# CPU_PCIE_USB_HDMI_EXT_PCIEX2_mPCIeX2.net
KiCad netlist of a schematic drawn in Altium Designer
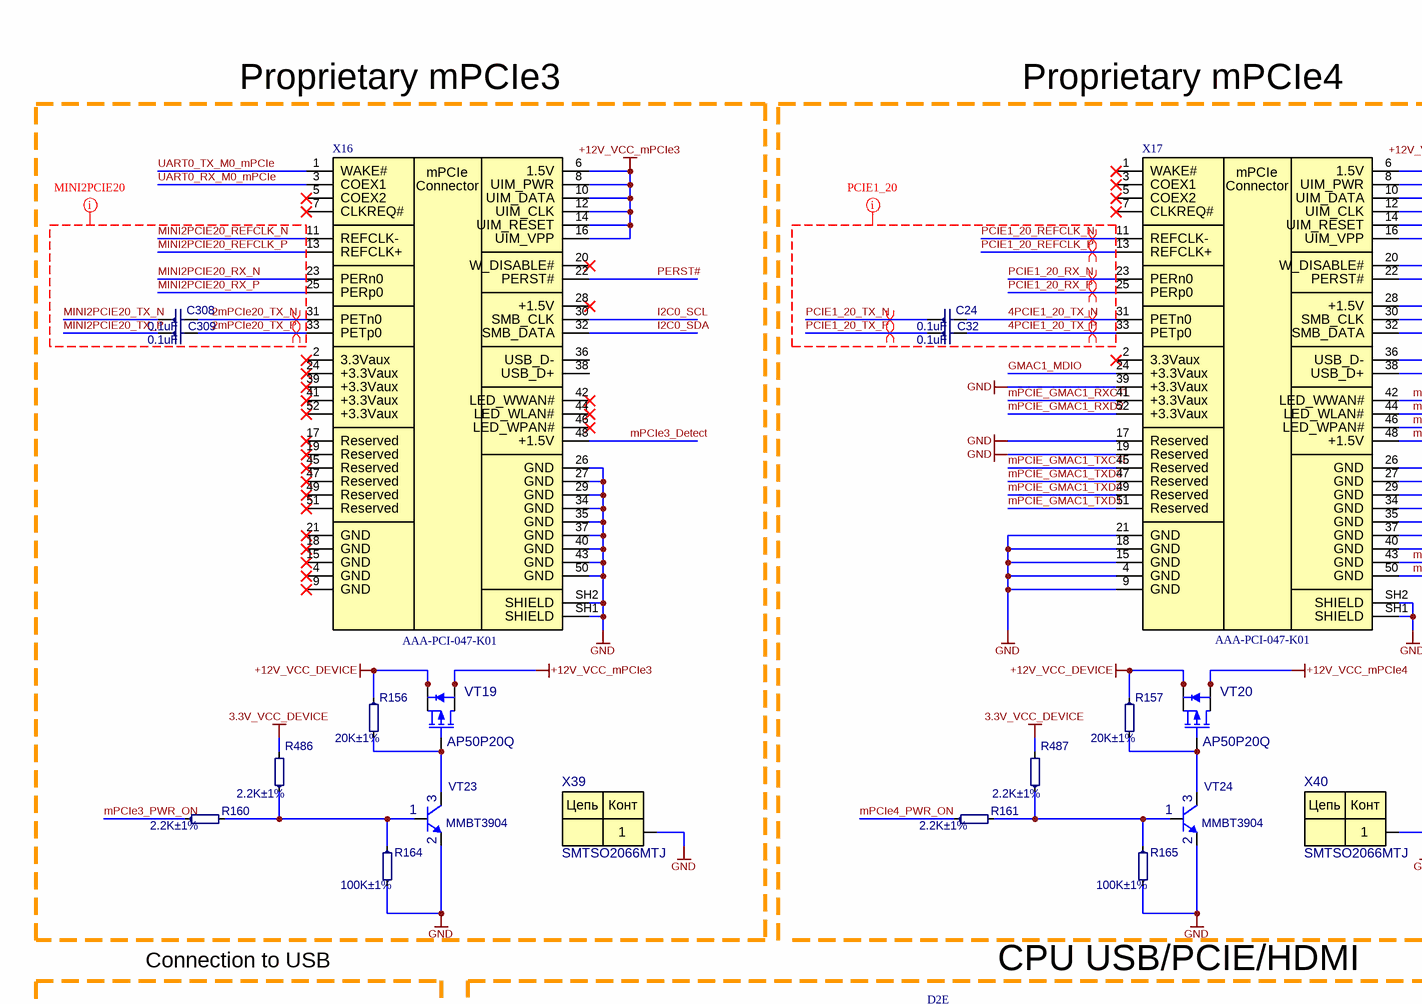
[diagram p0: CPU_PCIE_USB_HDMI_EXT_PCIEX2_mPCIeX2.SchDoc, top left]
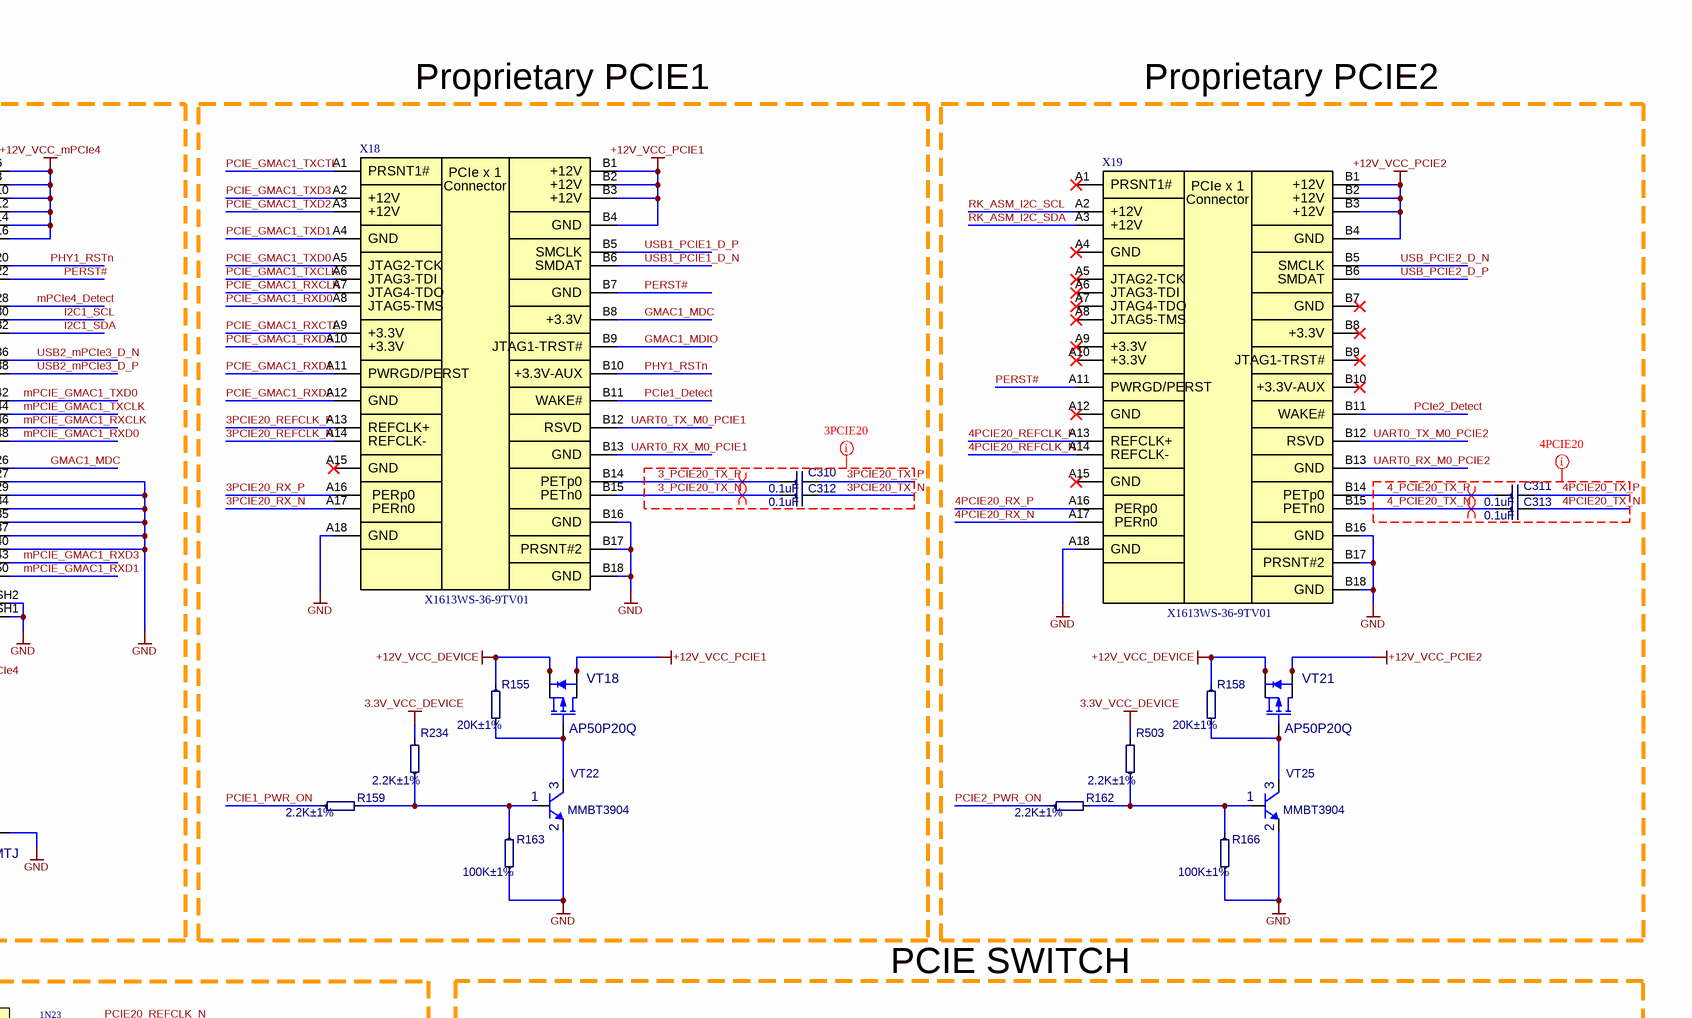
[diagram p1: CPU_PCIE_USB_HDMI_EXT_PCIEX2_mPCIeX2.SchDoc, top right]
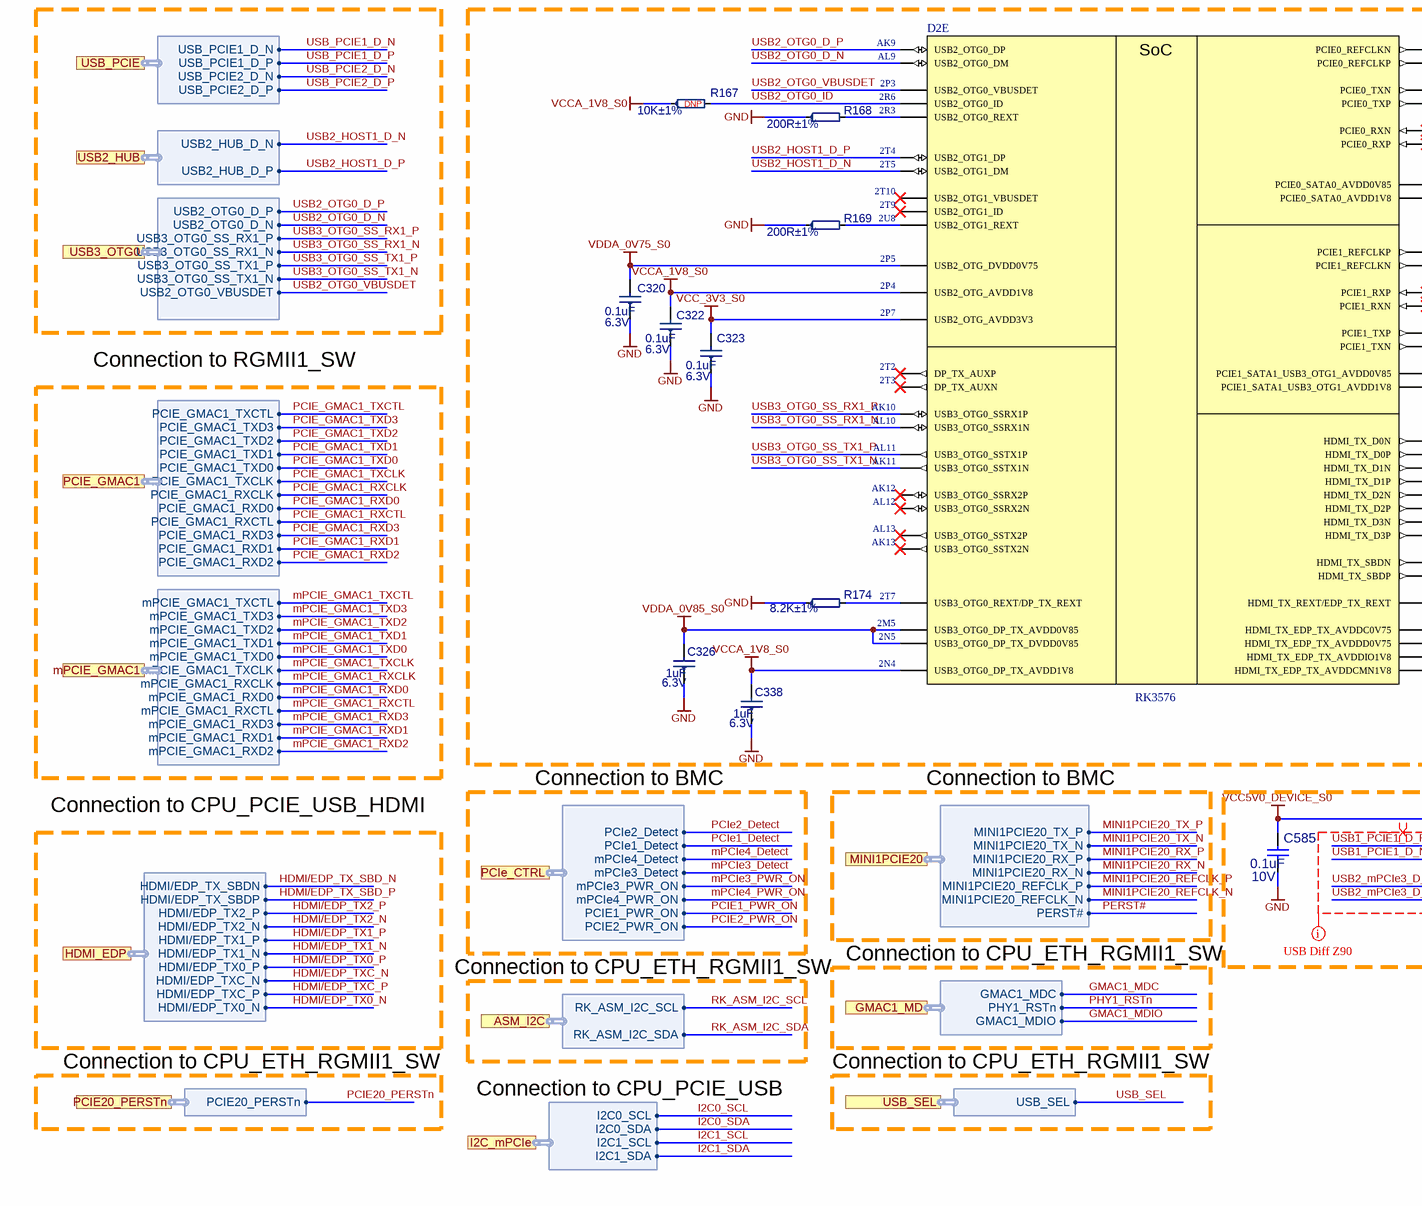
[diagram p2: CPU_PCIE_USB_HDMI_EXT_PCIEX2_mPCIeX2.SchDoc, bottom left]
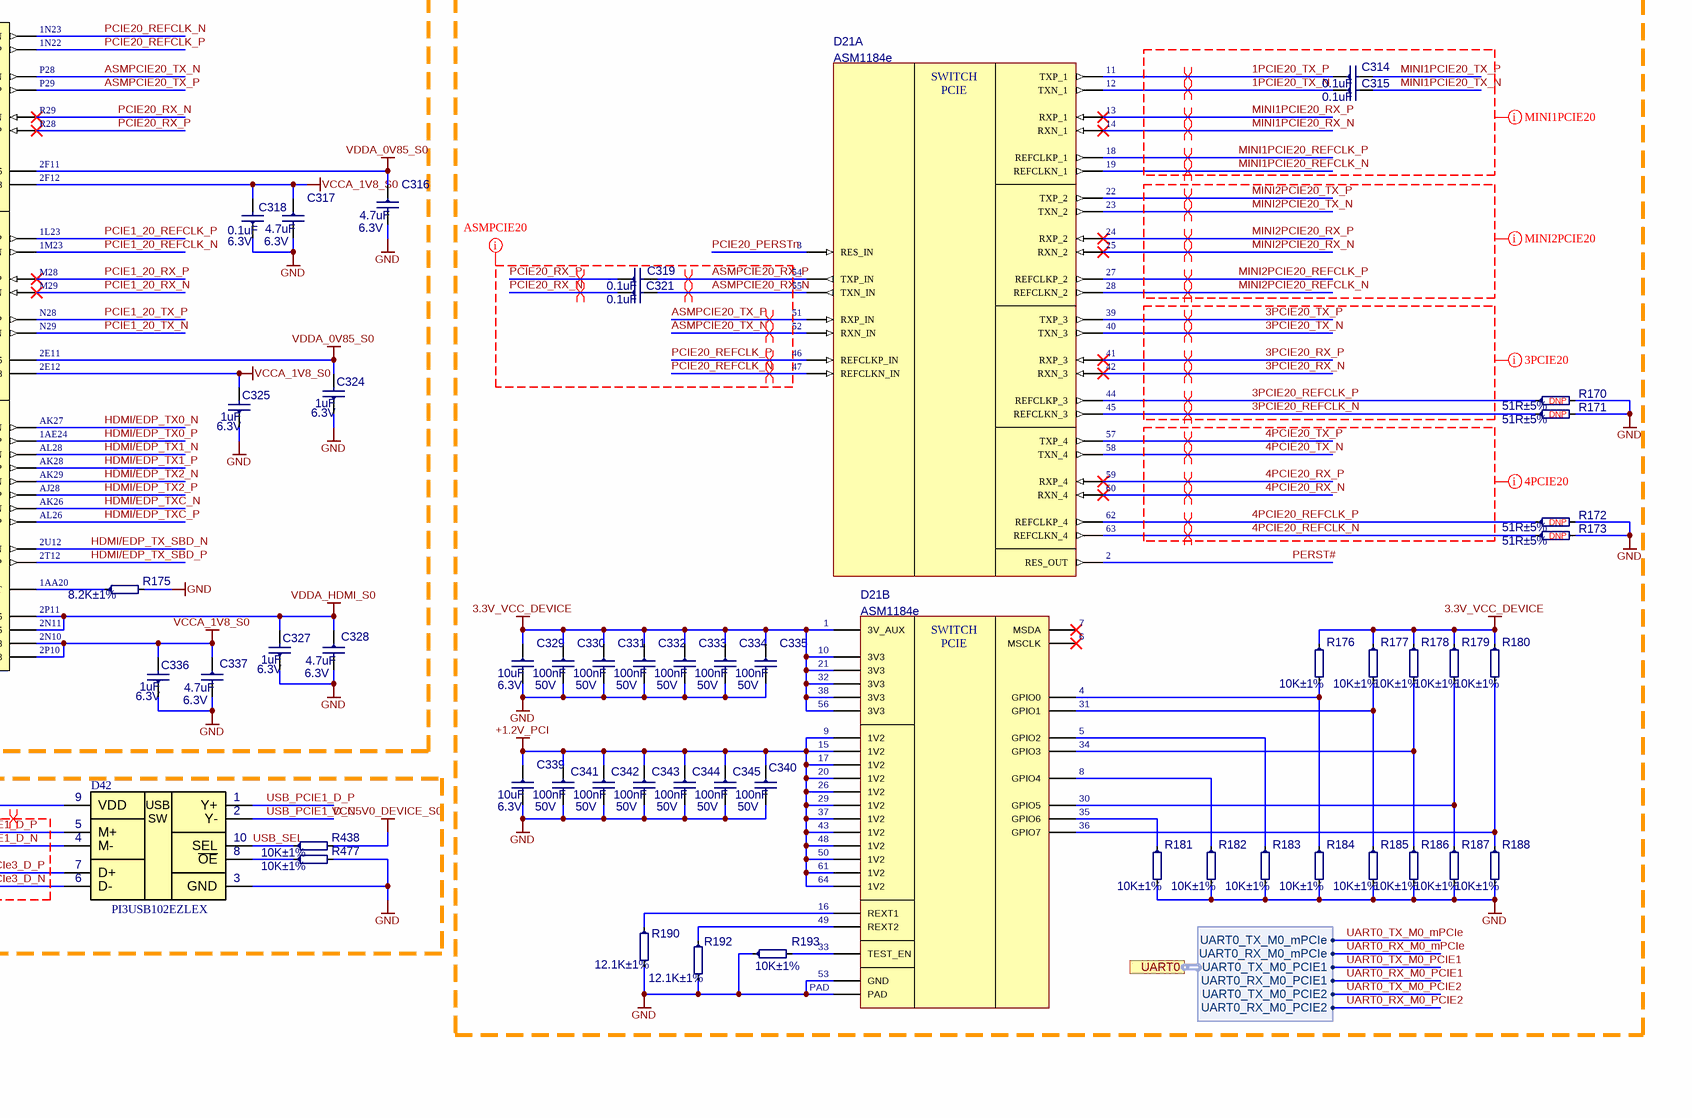
[diagram p3: CPU_PCIE_USB_HDMI_EXT_PCIEX2_mPCIeX2.SchDoc, bottom right]

(export (version "E")
  (design (tool "Eeschema 10.0.6"))
  (components
    (comp (ref "C24")
      (value "0.1uF")
      (footprint "C0201")
      (fields
        (field (name "VOLTAGE") "25V")
        (field (name "PART NUMBER") "0201-X5R-25V-0.1uF±10%")
        (field (name "TOLERANCE") "10%")
      )
      (libsource (lib "ATB") (part "C"))
    )
    (comp (ref "C32")
      (value "0.1uF")
      (footprint "C0201")
      (fields
        (field (name "VOLTAGE") "25V")
        (field (name "PART NUMBER") "0201-X5R-25V-0.1uF±10%")
        (field (name "TOLERANCE") "10%")
      )
      (libsource (lib "ATB") (part "C"))
    )
    (comp (ref "C308")
      (value "0.1uF")
      (footprint "C0201")
      (fields
        (field (name "VOLTAGE") "25V")
        (field (name "PART NUMBER") "0201-X5R-25V-0.1uF±10%")
        (field (name "TOLERANCE") "10%")
      )
      (libsource (lib "ATB") (part "C"))
    )
    (comp (ref "C309")
      (value "0.1uF")
      (footprint "C0201")
      (fields
        (field (name "VOLTAGE") "25V")
        (field (name "PART NUMBER") "0201-X5R-25V-0.1uF±10%")
        (field (name "TOLERANCE") "10%")
      )
      (libsource (lib "ATB") (part "C"))
    )
    (comp (ref "C310")
      (value "0.1uF")
      (footprint "C0201")
      (fields
        (field (name "VOLTAGE") "25V")
        (field (name "PART NUMBER") "0201-X5R-25V-0.1uF±10%")
        (field (name "TOLERANCE") "10%")
      )
      (libsource (lib "ATB") (part "C"))
    )
    (comp (ref "C311")
      (value "0.1uF")
      (footprint "C0201")
      (fields
        (field (name "VOLTAGE") "25V")
        (field (name "PART NUMBER") "0201-X5R-25V-0.1uF±10%")
        (field (name "TOLERANCE") "10%")
      )
      (libsource (lib "ATB") (part "C"))
    )
    (comp (ref "C312")
      (value "0.1uF")
      (footprint "C0201")
      (fields
        (field (name "VOLTAGE") "25V")
        (field (name "PART NUMBER") "0201-X5R-25V-0.1uF±10%")
        (field (name "TOLERANCE") "10%")
      )
      (libsource (lib "ATB") (part "C"))
    )
    (comp (ref "C313")
      (value "0.1uF")
      (footprint "C0201")
      (fields
        (field (name "VOLTAGE") "25V")
        (field (name "PART NUMBER") "0201-X5R-25V-0.1uF±10%")
        (field (name "TOLERANCE") "10%")
      )
      (libsource (lib "ATB") (part "C"))
    )
    (comp (ref "C314")
      (value "0.1uF")
      (footprint "C0201")
      (fields
        (field (name "VOLTAGE") "25V")
        (field (name "PART NUMBER") "0201-X5R-25V-0.1uF±10%")
        (field (name "TOLERANCE") "10%")
      )
      (libsource (lib "ATB") (part "C"))
    )
    (comp (ref "C315")
      (value "0.1uF")
      (footprint "C0201")
      (fields
        (field (name "VOLTAGE") "25V")
        (field (name "PART NUMBER") "0201-X5R-25V-0.1uF±10%")
        (field (name "TOLERANCE") "10%")
      )
      (libsource (lib "ATB") (part "C"))
    )
    (comp (ref "C316")
      (value "4.7uF")
      (footprint "C0201")
      (fields
        (field (name "VOLTAGE") "6.3V")
        (field (name "PART NUMBER") "0201-X5R-6.3V-4.7uF±20%")
        (field (name "TOLERANCE") "20%")
        (field (name "MANUFACTURER") "Murata Electronics")
      )
      (libsource (lib "ATB") (part "C"))
    )
    (comp (ref "C317")
      (value "4.7uF")
      (footprint "C0201")
      (fields
        (field (name "VOLTAGE") "6.3V")
        (field (name "PART NUMBER") "0201-X5R-6.3V-4.7uF±20%")
        (field (name "TOLERANCE") "20%")
        (field (name "MANUFACTURER") "Murata Electronics")
      )
      (libsource (lib "ATB") (part "C"))
    )
    (comp (ref "C318")
      (value "0.1uF")
      (footprint "C0201")
      (fields
        (field (name "VOLTAGE") "6.3V")
        (field (name "PART NUMBER") "0201-X5R-6.3V-0.1uF±10%")
        (field (name "TOLERANCE") "10%")
        (field (name "MANUFACTURER") "Yageo")
      )
      (libsource (lib "ATB") (part "C"))
    )
    (comp (ref "C319")
      (value "0.1uF")
      (footprint "C0201")
      (fields
        (field (name "VOLTAGE") "25V")
        (field (name "PART NUMBER") "0201-X5R-25V-0.1uF±10%")
        (field (name "TOLERANCE") "10%")
      )
      (libsource (lib "ATB") (part "C"))
    )
    (comp (ref "C320")
      (value "0.1uF")
      (footprint "C0201")
      (fields
        (field (name "VOLTAGE") "6.3V")
        (field (name "PART NUMBER") "0201-X5R-6.3V-0.1uF±10%")
        (field (name "TOLERANCE") "10%")
        (field (name "MANUFACTURER") "Yageo")
      )
      (libsource (lib "ATB") (part "C"))
    )
    (comp (ref "C321")
      (value "0.1uF")
      (footprint "C0201")
      (fields
        (field (name "VOLTAGE") "25V")
        (field (name "PART NUMBER") "0201-X5R-25V-0.1uF±10%")
        (field (name "TOLERANCE") "10%")
      )
      (libsource (lib "ATB") (part "C"))
    )
    (comp (ref "C322")
      (value "0.1uF")
      (footprint "C0201")
      (fields
        (field (name "VOLTAGE") "6.3V")
        (field (name "PART NUMBER") "0201-X5R-6.3V-0.1uF±10%")
        (field (name "TOLERANCE") "10%")
        (field (name "MANUFACTURER") "Yageo")
      )
      (libsource (lib "ATB") (part "C"))
    )
    (comp (ref "C323")
      (value "0.1uF")
      (footprint "C0201")
      (fields
        (field (name "VOLTAGE") "6.3V")
        (field (name "PART NUMBER") "0201-X5R-6.3V-0.1uF±10%")
        (field (name "TOLERANCE") "10%")
        (field (name "MANUFACTURER") "Yageo")
      )
      (libsource (lib "ATB") (part "C"))
    )
    (comp (ref "C324")
      (value "1uF")
      (footprint "C0201")
      (fields
        (field (name "VOLTAGE") "6.3V")
        (field (name "PART NUMBER") "0201-X5R-6.3V-1uF±20%")
        (field (name "TOLERANCE") "20%")
        (field (name "MANUFACTURER") "Murata Electronics")
      )
      (libsource (lib "ATB") (part "C"))
    )
    (comp (ref "C325")
      (value "1uF")
      (footprint "C0201")
      (fields
        (field (name "VOLTAGE") "6.3V")
        (field (name "PART NUMBER") "0201-X5R-6.3V-1uF±20%")
        (field (name "TOLERANCE") "20%")
        (field (name "MANUFACTURER") "Murata Electronics")
      )
      (libsource (lib "ATB") (part "C"))
    )
    (comp (ref "C326")
      (value "1uF")
      (footprint "C0201")
      (fields
        (field (name "VOLTAGE") "6.3V")
        (field (name "PART NUMBER") "0201-X5R-6.3V-1uF±20%")
        (field (name "TOLERANCE") "20%")
        (field (name "MANUFACTURER") "Murata Electronics")
      )
      (libsource (lib "ATB") (part "C"))
    )
    (comp (ref "C327")
      (value "1uF")
      (footprint "C0201")
      (fields
        (field (name "VOLTAGE") "6.3V")
        (field (name "PART NUMBER") "0201-X5R-6.3V-1uF±20%")
        (field (name "TOLERANCE") "20%")
        (field (name "MANUFACTURER") "Murata Electronics")
      )
      (libsource (lib "ATB") (part "C"))
    )
    (comp (ref "C328")
      (value "4.7uF")
      (footprint "C0201")
      (fields
        (field (name "VOLTAGE") "6.3V")
        (field (name "PART NUMBER") "0201-X5R-6.3V-4.7uF±20%")
        (field (name "TOLERANCE") "20%")
        (field (name "MANUFACTURER") "Murata Electronics")
      )
      (libsource (lib "ATB") (part "C"))
    )
    (comp (ref "C329")
      (value "10uF")
      (footprint "C0402")
      (fields
        (field (name "VOLTAGE") "6.3V")
        (field (name "PART NUMBER") "0402-X5R-6.3V-10uF±20%")
        (field (name "TOLERANCE") "20%")
        (field (name "MANUFACTURER") "Yageo")
      )
      (libsource (lib "ATB") (part "C"))
    )
    (comp (ref "C330")
      (value "100nF")
      (footprint "C0402")
      (description "Ceramic Capacitor 0402 100nF ±10% 50V X7R")
      (fields
        (field (name "VOLTAGE") "50V")
        (field (name "PART NUMBER") "0402-X7R-50V-0.1uF±10%")
        (field (name "TOLERANCE") "10%")
      )
      (libsource (lib "ATB") (part "C"))
    )
    (comp (ref "C331")
      (value "100nF")
      (footprint "C0402")
      (description "Ceramic Capacitor 0402 100nF ±10% 50V X7R")
      (fields
        (field (name "VOLTAGE") "50V")
        (field (name "PART NUMBER") "0402-X7R-50V-0.1uF±10%")
        (field (name "TOLERANCE") "10%")
      )
      (libsource (lib "ATB") (part "C"))
    )
    (comp (ref "C332")
      (value "100nF")
      (footprint "C0402")
      (description "Ceramic Capacitor 0402 100nF ±10% 50V X7R")
      (fields
        (field (name "VOLTAGE") "50V")
        (field (name "PART NUMBER") "0402-X7R-50V-0.1uF±10%")
        (field (name "TOLERANCE") "10%")
      )
      (libsource (lib "ATB") (part "C"))
    )
    (comp (ref "C333")
      (value "100nF")
      (footprint "C0402")
      (description "Ceramic Capacitor 0402 100nF ±10% 50V X7R")
      (fields
        (field (name "VOLTAGE") "50V")
        (field (name "PART NUMBER") "0402-X7R-50V-0.1uF±10%")
        (field (name "TOLERANCE") "10%")
      )
      (libsource (lib "ATB") (part "C"))
    )
    (comp (ref "C334")
      (value "100nF")
      (footprint "C0402")
      (description "Ceramic Capacitor 0402 100nF ±10% 50V X7R")
      (fields
        (field (name "VOLTAGE") "50V")
        (field (name "PART NUMBER") "0402-X7R-50V-0.1uF±10%")
        (field (name "TOLERANCE") "10%")
      )
      (libsource (lib "ATB") (part "C"))
    )
    (comp (ref "C335")
      (value "100nF")
      (footprint "C0402")
      (description "Ceramic Capacitor 0402 100nF ±10% 50V X7R")
      (fields
        (field (name "VOLTAGE") "50V")
        (field (name "PART NUMBER") "0402-X7R-50V-0.1uF±10%")
        (field (name "TOLERANCE") "10%")
      )
      (libsource (lib "ATB") (part "C"))
    )
    (comp (ref "C336")
      (value "1uF")
      (footprint "C0201")
      (fields
        (field (name "VOLTAGE") "6.3V")
        (field (name "PART NUMBER") "0201-X5R-6.3V-1uF±20%")
        (field (name "TOLERANCE") "20%")
        (field (name "MANUFACTURER") "Murata Electronics")
      )
      (libsource (lib "ATB") (part "C"))
    )
    (comp (ref "C337")
      (value "4.7uF")
      (footprint "C0201")
      (fields
        (field (name "VOLTAGE") "6.3V")
        (field (name "PART NUMBER") "0201-X5R-6.3V-4.7uF±20%")
        (field (name "TOLERANCE") "20%")
        (field (name "MANUFACTURER") "Murata Electronics")
      )
      (libsource (lib "ATB") (part "C"))
    )
    (comp (ref "C338")
      (value "1uF")
      (footprint "C0201")
      (fields
        (field (name "VOLTAGE") "6.3V")
        (field (name "PART NUMBER") "0201-X5R-6.3V-1uF±20%")
        (field (name "TOLERANCE") "20%")
        (field (name "MANUFACTURER") "Murata Electronics")
      )
      (libsource (lib "ATB") (part "C"))
    )
    (comp (ref "C339")
      (value "10uF")
      (footprint "C0402")
      (fields
        (field (name "VOLTAGE") "6.3V")
        (field (name "PART NUMBER") "0402-X5R-6.3V-10uF±20%")
        (field (name "TOLERANCE") "20%")
        (field (name "MANUFACTURER") "Yageo")
      )
      (libsource (lib "ATB") (part "C"))
    )
    (comp (ref "C340")
      (value "100nF")
      (footprint "C0402")
      (description "Ceramic Capacitor 0402 100nF ±10% 50V X7R")
      (fields
        (field (name "VOLTAGE") "50V")
        (field (name "PART NUMBER") "0402-X7R-50V-0.1uF±10%")
        (field (name "TOLERANCE") "10%")
      )
      (libsource (lib "ATB") (part "C"))
    )
    (comp (ref "C341")
      (value "100nF")
      (footprint "C0402")
      (description "Ceramic Capacitor 0402 100nF ±10% 50V X7R")
      (fields
        (field (name "VOLTAGE") "50V")
        (field (name "PART NUMBER") "0402-X7R-50V-0.1uF±10%")
        (field (name "TOLERANCE") "10%")
      )
      (libsource (lib "ATB") (part "C"))
    )
    (comp (ref "C342")
      (value "100nF")
      (footprint "C0402")
      (description "Ceramic Capacitor 0402 100nF ±10% 50V X7R")
      (fields
        (field (name "VOLTAGE") "50V")
        (field (name "PART NUMBER") "0402-X7R-50V-0.1uF±10%")
        (field (name "TOLERANCE") "10%")
      )
      (libsource (lib "ATB") (part "C"))
    )
    (comp (ref "C343")
      (value "100nF")
      (footprint "C0402")
      (description "Ceramic Capacitor 0402 100nF ±10% 50V X7R")
      (fields
        (field (name "VOLTAGE") "50V")
        (field (name "PART NUMBER") "0402-X7R-50V-0.1uF±10%")
        (field (name "TOLERANCE") "10%")
      )
      (libsource (lib "ATB") (part "C"))
    )
    (comp (ref "C344")
      (value "100nF")
      (footprint "C0402")
      (description "Ceramic Capacitor 0402 100nF ±10% 50V X7R")
      (fields
        (field (name "VOLTAGE") "50V")
        (field (name "PART NUMBER") "0402-X7R-50V-0.1uF±10%")
        (field (name "TOLERANCE") "10%")
      )
      (libsource (lib "ATB") (part "C"))
    )
    (comp (ref "C345")
      (value "100nF")
      (footprint "C0402")
      (description "Ceramic Capacitor 0402 100nF ±10% 50V X7R")
      (fields
        (field (name "VOLTAGE") "50V")
        (field (name "PART NUMBER") "0402-X7R-50V-0.1uF±10%")
        (field (name "TOLERANCE") "10%")
      )
      (libsource (lib "ATB") (part "C"))
    )
    (comp (ref "C585")
      (value "0.1uF")
      (footprint "C0402")
      (fields
        (field (name "PART NUMBER") "0402-X5R-10V-0.1uF±10%")
        (field (name "VOLTAGE") "10V")
        (field (name "TOLERANCE") "10%")
        (field (name "MANUFACTURER") "Yageo")
      )
      (libsource (lib "") (part "C_1"))
    )
    (comp (ref "D2")
      (value "RK3576")
      (footprint "BGAFCCSP698L")
      (description "SoC 4xCortex-A72@2.2Ghz+4xCortex-A53@2Ghz, LPDDR4/4X/5/5X, SDIO/eMMC/UFS/FSPI, BGA 16.1x17.2x1.0mm")
      (fields (field (name "MANUFACTURER") "Rockship"))
      (libsource (lib "ATB") (part "RK3576"))
    )
    (comp (ref "D21")
      (value "ASM1184e")
      (footprint "QFN50X90X90X09-64T75x75")
      (description "Interface PCIE switch, PCIEx1 to 4xPCIEx1, 3.0V~3.6V, QFN-64 9.0x9.0x0.9mm 0.5mm pitch")
      (fields (field (name "MANUFACTURER") "ASMedia"))
      (libsource (lib "ATB") (part "ASM1184e"))
    )
    (comp (ref "D42")
      (value "PI3USB102EZLEX")
      (footprint "PI3USB102EZLEX")
      (description "USB 2.0 High-Speed (480 Mbps)  Switch with 5V Protection")
      (fields (field (name "MANUFACTURER") "Diodes"))
      (libsource (lib "LIB_RK") (part "PI3USB102EZLEX"))
    )
    (comp (ref "R155")
      (value "20K±1%")
      (footprint "R0402")
      (description "Chip Resistor 0402 20kΩ ±1% 50V ±100ppm/℃ Thick Film")
      (fields (field (name "PART NUMBER") "0402-0.0625W-20K-100ppm±1%") (field (name "TOLERANCE") "1%"))
      (libsource (lib "ATB") (part "R"))
    )
    (comp (ref "R156")
      (value "20K±1%")
      (footprint "R0402")
      (description "Chip Resistor 0402 20kΩ ±1% 50V ±100ppm/℃ Thick Film")
      (fields (field (name "PART NUMBER") "0402-0.0625W-20K-100ppm±1%") (field (name "TOLERANCE") "1%"))
      (libsource (lib "ATB") (part "R"))
    )
    (comp (ref "R157")
      (value "20K±1%")
      (footprint "R0402")
      (description "Chip Resistor 0402 20kΩ ±1% 50V ±100ppm/℃ Thick Film")
      (fields (field (name "PART NUMBER") "0402-0.0625W-20K-100ppm±1%") (field (name "TOLERANCE") "1%"))
      (libsource (lib "ATB") (part "R"))
    )
    (comp (ref "R158")
      (value "20K±1%")
      (footprint "R0402")
      (description "Chip Resistor 0402 20kΩ ±1% 50V ±100ppm/℃ Thick Film")
      (fields (field (name "PART NUMBER") "0402-0.0625W-20K-100ppm±1%") (field (name "TOLERANCE") "1%"))
      (libsource (lib "ATB") (part "R"))
    )
    (comp (ref "R159")
      (value "2.2K±1%")
      (footprint "R0402")
      (fields
        (field (name "PART NUMBER") "0402-0.0625W-2.2K-100ppm±1%")
        (field (name "TOLERANCE") "1%")
        (field (name "MANUFACTURER") "Yageo")
      )
      (libsource (lib "ATB") (part "R"))
    )
    (comp (ref "R160")
      (value "2.2K±1%")
      (footprint "R0402")
      (fields
        (field (name "PART NUMBER") "0402-0.0625W-2.2K-100ppm±1%")
        (field (name "TOLERANCE") "1%")
        (field (name "MANUFACTURER") "Yageo")
      )
      (libsource (lib "ATB") (part "R"))
    )
    (comp (ref "R161")
      (value "2.2K±1%")
      (footprint "R0402")
      (fields
        (field (name "PART NUMBER") "0402-0.0625W-2.2K-100ppm±1%")
        (field (name "TOLERANCE") "1%")
        (field (name "MANUFACTURER") "Yageo")
      )
      (libsource (lib "ATB") (part "R"))
    )
    (comp (ref "R162")
      (value "2.2K±1%")
      (footprint "R0402")
      (fields
        (field (name "PART NUMBER") "0402-0.0625W-2.2K-100ppm±1%")
        (field (name "TOLERANCE") "1%")
        (field (name "MANUFACTURER") "Yageo")
      )
      (libsource (lib "ATB") (part "R"))
    )
    (comp (ref "R163")
      (value "100K±1%")
      (footprint "R0402")
      (description "Chip Resistor 0402 100kΩ ±1% 50V ±100ppm/℃ Thick Film")
      (fields (field (name "PART NUMBER") "0402-0.0625W-100K-100ppm±1%") (field (name "TOLERANCE") "1%"))
      (libsource (lib "ATB") (part "R"))
    )
    (comp (ref "R164")
      (value "100K±1%")
      (footprint "R0402")
      (description "Chip Resistor 0402 100kΩ ±1% 50V ±100ppm/℃ Thick Film")
      (fields (field (name "PART NUMBER") "0402-0.0625W-100K-100ppm±1%") (field (name "TOLERANCE") "1%"))
      (libsource (lib "ATB") (part "R"))
    )
    (comp (ref "R165")
      (value "100K±1%")
      (footprint "R0402")
      (description "Chip Resistor 0402 100kΩ ±1% 50V ±100ppm/℃ Thick Film")
      (fields (field (name "PART NUMBER") "0402-0.0625W-100K-100ppm±1%") (field (name "TOLERANCE") "1%"))
      (libsource (lib "ATB") (part "R"))
    )
    (comp (ref "R166")
      (value "100K±1%")
      (footprint "R0402")
      (description "Chip Resistor 0402 100kΩ ±1% 50V ±100ppm/℃ Thick Film")
      (fields (field (name "PART NUMBER") "0402-0.0625W-100K-100ppm±1%") (field (name "TOLERANCE") "1%"))
      (libsource (lib "ATB") (part "R"))
    )
    (comp (ref "R167")
      (value "10K±1%")
      (footprint "R0402")
      (description "Chip Resistor 0402 10kΩ ±1% 50V ±100ppm/℃ Thick Film")
      (fields (field (name "PART NUMBER") "0402-0.0625W-10K-100ppm±1%") (field (name "TOLERANCE") "1%"))
      (libsource (lib "ATB") (part "R"))
    )
    (comp (ref "R168")
      (value "200R±1%")
      (footprint "R0402")
      (fields
        (field (name "PART NUMBER") "0402-0.0625W-200R-100ppm±1%")
        (field (name "TOLERANCE") "1%")
        (field (name "MANUFACTURER") "Vishay Intertechnology Inc.")
      )
      (libsource (lib "ATB") (part "R"))
    )
    (comp (ref "R169")
      (value "200R±1%")
      (footprint "R0402")
      (fields
        (field (name "PART NUMBER") "0402-0.0625W-200R-100ppm±1%")
        (field (name "TOLERANCE") "1%")
        (field (name "MANUFACTURER") "Vishay Intertechnology Inc.")
      )
      (libsource (lib "ATB") (part "R"))
    )
    (comp (ref "R170")
      (value "51R±5%")
      (footprint "R0402")
      (fields
        (field (name "PART NUMBER") "0402-0.0625W-51R-200ppm±5%")
        (field (name "TOLERANCE") "5%")
        (field (name "MANUFACTURER") "Yageo")
      )
      (libsource (lib "ATB") (part "R"))
    )
    (comp (ref "R171")
      (value "51R±5%")
      (footprint "R0402")
      (fields
        (field (name "PART NUMBER") "0402-0.0625W-51R-200ppm±5%")
        (field (name "TOLERANCE") "5%")
        (field (name "MANUFACTURER") "Yageo")
      )
      (libsource (lib "ATB") (part "R"))
    )
    (comp (ref "R172")
      (value "51R±5%")
      (footprint "R0402")
      (fields
        (field (name "PART NUMBER") "0402-0.0625W-51R-200ppm±5%")
        (field (name "TOLERANCE") "5%")
        (field (name "MANUFACTURER") "Yageo")
      )
      (libsource (lib "ATB") (part "R"))
    )
    (comp (ref "R173")
      (value "51R±5%")
      (footprint "R0402")
      (fields
        (field (name "PART NUMBER") "0402-0.0625W-51R-200ppm±5%")
        (field (name "TOLERANCE") "5%")
        (field (name "MANUFACTURER") "Yageo")
      )
      (libsource (lib "ATB") (part "R"))
    )
    (comp (ref "R174")
      (value "8.2K±1%")
      (footprint "R0402")
      (fields
        (field (name "PART NUMBER") "0402-0.0625W-8.2K-100ppm±1%")
        (field (name "TOLERANCE") "1%")
        (field (name "MANUFACTURER") "Yageo")
      )
      (libsource (lib "ATB") (part "R"))
    )
    (comp (ref "R175")
      (value "8.2K±1%")
      (footprint "R0402")
      (fields
        (field (name "PART NUMBER") "0402-0.0625W-8.2K-100ppm±1%")
        (field (name "TOLERANCE") "1%")
        (field (name "MANUFACTURER") "Yageo")
      )
      (libsource (lib "ATB") (part "R"))
    )
    (comp (ref "R176")
      (value "10K±1%")
      (footprint "R0402")
      (description "Chip Resistor 0402 10kΩ ±1% 50V ±100ppm/℃ Thick Film")
      (fields (field (name "PART NUMBER") "0402-0.0625W-10K-100ppm±1%") (field (name "TOLERANCE") "1%"))
      (libsource (lib "ATB") (part "R"))
    )
    (comp (ref "R177")
      (value "10K±1%")
      (footprint "R0402")
      (description "Chip Resistor 0402 10kΩ ±1% 50V ±100ppm/℃ Thick Film")
      (fields (field (name "PART NUMBER") "0402-0.0625W-10K-100ppm±1%") (field (name "TOLERANCE") "1%"))
      (libsource (lib "ATB") (part "R"))
    )
    (comp (ref "R178")
      (value "10K±1%")
      (footprint "R0402")
      (description "Chip Resistor 0402 10kΩ ±1% 50V ±100ppm/℃ Thick Film")
      (fields (field (name "PART NUMBER") "0402-0.0625W-10K-100ppm±1%") (field (name "TOLERANCE") "1%"))
      (libsource (lib "ATB") (part "R"))
    )
    (comp (ref "R179")
      (value "10K±1%")
      (footprint "R0402")
      (description "Chip Resistor 0402 10kΩ ±1% 50V ±100ppm/℃ Thick Film")
      (fields (field (name "PART NUMBER") "0402-0.0625W-10K-100ppm±1%") (field (name "TOLERANCE") "1%"))
      (libsource (lib "ATB") (part "R"))
    )
    (comp (ref "R180")
      (value "10K±1%")
      (footprint "R0402")
      (description "Chip Resistor 0402 10kΩ ±1% 50V ±100ppm/℃ Thick Film")
      (fields (field (name "PART NUMBER") "0402-0.0625W-10K-100ppm±1%") (field (name "TOLERANCE") "1%"))
      (libsource (lib "ATB") (part "R"))
    )
    (comp (ref "R181")
      (value "10K±1%")
      (footprint "R0402")
      (description "Chip Resistor 0402 10kΩ ±1% 50V ±100ppm/℃ Thick Film")
      (fields (field (name "PART NUMBER") "0402-0.0625W-10K-100ppm±1%") (field (name "TOLERANCE") "1%"))
      (libsource (lib "ATB") (part "R"))
    )
    (comp (ref "R182")
      (value "10K±1%")
      (footprint "R0402")
      (description "Chip Resistor 0402 10kΩ ±1% 50V ±100ppm/℃ Thick Film")
      (fields (field (name "PART NUMBER") "0402-0.0625W-10K-100ppm±1%") (field (name "TOLERANCE") "1%"))
      (libsource (lib "ATB") (part "R"))
    )
    (comp (ref "R183")
      (value "10K±1%")
      (footprint "R0402")
      (description "Chip Resistor 0402 10kΩ ±1% 50V ±100ppm/℃ Thick Film")
      (fields (field (name "PART NUMBER") "0402-0.0625W-10K-100ppm±1%") (field (name "TOLERANCE") "1%"))
      (libsource (lib "ATB") (part "R"))
    )
    (comp (ref "R184")
      (value "10K±1%")
      (footprint "R0402")
      (description "Chip Resistor 0402 10kΩ ±1% 50V ±100ppm/℃ Thick Film")
      (fields (field (name "PART NUMBER") "0402-0.0625W-10K-100ppm±1%") (field (name "TOLERANCE") "1%"))
      (libsource (lib "ATB") (part "R"))
    )
    (comp (ref "R185")
      (value "10K±1%")
      (footprint "R0402")
      (description "Chip Resistor 0402 10kΩ ±1% 50V ±100ppm/℃ Thick Film")
      (fields (field (name "PART NUMBER") "0402-0.0625W-10K-100ppm±1%") (field (name "TOLERANCE") "1%"))
      (libsource (lib "ATB") (part "R"))
    )
    (comp (ref "R186")
      (value "10K±1%")
      (footprint "R0402")
      (description "Chip Resistor 0402 10kΩ ±1% 50V ±100ppm/℃ Thick Film")
      (fields (field (name "PART NUMBER") "0402-0.0625W-10K-100ppm±1%") (field (name "TOLERANCE") "1%"))
      (libsource (lib "ATB") (part "R"))
    )
    (comp (ref "R187")
      (value "10K±1%")
      (footprint "R0402")
      (description "Chip Resistor 0402 10kΩ ±1% 50V ±100ppm/℃ Thick Film")
      (fields (field (name "PART NUMBER") "0402-0.0625W-10K-100ppm±1%") (field (name "TOLERANCE") "1%"))
      (libsource (lib "ATB") (part "R"))
    )
    (comp (ref "R188")
      (value "10K±1%")
      (footprint "R0402")
      (description "Chip Resistor 0402 10kΩ ±1% 50V ±100ppm/℃ Thick Film")
      (fields (field (name "PART NUMBER") "0402-0.0625W-10K-100ppm±1%") (field (name "TOLERANCE") "1%"))
      (libsource (lib "ATB") (part "R"))
    )
    (comp (ref "R190")
      (value "12.1K±1%")
      (footprint "R0402")
      (description "Chip Resistor 0402 12.1kΩ ±1% 50V ±100ppm/℃ Thick Film")
      (fields (field (name "PART NUMBER") "0402-0.0625W-12.1K-100ppm±1%") (field (name "TOLERANCE") "1%"))
      (libsource (lib "ATB") (part "R"))
    )
    (comp (ref "R192")
      (value "12.1K±1%")
      (footprint "R0402")
      (description "Chip Resistor 0402 12.1kΩ ±1% 50V ±100ppm/℃ Thick Film")
      (fields (field (name "PART NUMBER") "0402-0.0625W-12.1K-100ppm±1%") (field (name "TOLERANCE") "1%"))
      (libsource (lib "ATB") (part "R"))
    )
    (comp (ref "R193")
      (value "10K±1%")
      (footprint "R0402")
      (description "Chip Resistor 0402 10kΩ ±1% 50V ±100ppm/℃ Thick Film")
      (fields (field (name "PART NUMBER") "0402-0.0625W-10K-100ppm±1%") (field (name "TOLERANCE") "1%"))
      (libsource (lib "ATB") (part "R"))
    )
    (comp (ref "R234")
      (value "2.2K±1%")
      (footprint "R0402")
      (fields
        (field (name "PART NUMBER") "0402-0.0625W-2.2K-100ppm±1%")
        (field (name "TOLERANCE") "1%")
        (field (name "MANUFACTURER") "Yageo")
      )
      (libsource (lib "ATB") (part "R"))
    )
    (comp (ref "R438")
      (value "10K±1%")
      (footprint "R0402")
      (description "Chip Resistor 0402 10kΩ ±1% 50V ±100ppm/℃ Thick Film")
      (fields (field (name "PART NUMBER") "0402-0.0625W-10K-100ppm±1%") (field (name "TOLERANCE") "1%"))
      (libsource (lib "ATB") (part "R"))
    )
    (comp (ref "R477")
      (value "10K±1%")
      (footprint "R0402")
      (description "Chip Resistor 0402 10kΩ ±1% 50V ±100ppm/℃ Thick Film")
      (fields (field (name "PART NUMBER") "0402-0.0625W-10K-100ppm±1%") (field (name "TOLERANCE") "1%"))
      (libsource (lib "ATB") (part "R"))
    )
    (comp (ref "R486")
      (value "2.2K±1%")
      (footprint "R0402")
      (fields
        (field (name "PART NUMBER") "0402-0.0625W-2.2K-100ppm±1%")
        (field (name "TOLERANCE") "1%")
        (field (name "MANUFACTURER") "Yageo")
      )
      (libsource (lib "ATB") (part "R"))
    )
    (comp (ref "R487")
      (value "2.2K±1%")
      (footprint "R0402")
      (fields
        (field (name "PART NUMBER") "0402-0.0625W-2.2K-100ppm±1%")
        (field (name "TOLERANCE") "1%")
        (field (name "MANUFACTURER") "Yageo")
      )
      (libsource (lib "ATB") (part "R"))
    )
    (comp (ref "R503")
      (value "2.2K±1%")
      (footprint "R0402")
      (fields
        (field (name "PART NUMBER") "0402-0.0625W-2.2K-100ppm±1%")
        (field (name "TOLERANCE") "1%")
        (field (name "MANUFACTURER") "Yageo")
      )
      (libsource (lib "ATB") (part "R"))
    )
    (comp (ref "VT18")
      (value "AP50P20Q")
      (footprint "AP50P20Q")
      (description "20V 50A 40W 6.6mΩ@4.5V,15A 650mV@250uA P Channel WDFN-8(3x3) MOSFETs")
      (fields (field (name "MANUFACTURER") "ALLPOWER"))
      (libsource (lib "LIB_RK") (part "AP50P20Q"))
    )
    (comp (ref "VT19")
      (value "AP50P20Q")
      (footprint "AP50P20Q")
      (description "20V 50A 40W 6.6mΩ@4.5V,15A 650mV@250uA P Channel WDFN-8(3x3) MOSFETs")
      (fields (field (name "MANUFACTURER") "ALLPOWER"))
      (libsource (lib "LIB_RK") (part "AP50P20Q"))
    )
    (comp (ref "VT20")
      (value "AP50P20Q")
      (footprint "AP50P20Q")
      (description "20V 50A 40W 6.6mΩ@4.5V,15A 650mV@250uA P Channel WDFN-8(3x3) MOSFETs")
      (fields (field (name "MANUFACTURER") "ALLPOWER"))
      (libsource (lib "LIB_RK") (part "AP50P20Q"))
    )
    (comp (ref "VT21")
      (value "AP50P20Q")
      (footprint "AP50P20Q")
      (description "20V 50A 40W 6.6mΩ@4.5V,15A 650mV@250uA P Channel WDFN-8(3x3) MOSFETs")
      (fields (field (name "MANUFACTURER") "ALLPOWER"))
      (libsource (lib "LIB_RK") (part "AP50P20Q"))
    )
    (comp (ref "VT22")
      (value "MMBT3904")
      (footprint "SOT23")
      (description "NPN transistor")
      (fields (field (name "VOLTAGE") "40V") (field (name "MANUFACTURER") "Diotec Semiconductor"))
      (libsource (lib "ATB") (part "BC846BLT1G"))
    )
    (comp (ref "VT23")
      (value "MMBT3904")
      (footprint "SOT23")
      (description "NPN transistor")
      (fields (field (name "VOLTAGE") "40V") (field (name "MANUFACTURER") "Diotec Semiconductor"))
      (libsource (lib "ATB") (part "BC846BLT1G"))
    )
    (comp (ref "VT24")
      (value "MMBT3904")
      (footprint "SOT23")
      (description "NPN transistor")
      (fields (field (name "VOLTAGE") "40V") (field (name "MANUFACTURER") "Diotec Semiconductor"))
      (libsource (lib "ATB") (part "BC846BLT1G"))
    )
    (comp (ref "VT25")
      (value "MMBT3904")
      (footprint "SOT23")
      (description "NPN transistor")
      (fields (field (name "VOLTAGE") "40V") (field (name "MANUFACTURER") "Diotec Semiconductor"))
      (libsource (lib "ATB") (part "BC846BLT1G"))
    )
    (comp (ref "X16")
      (value "AAA-PCI-047-K01")
      (footprint "AAA-PCI-047-K01")
      (description "mPCI-E Surface Mount 52 SMD,P=0.8mm Card Edge Connectors")
      (fields (field (name "MANUFACTURER") "LOTES"))
      (libsource (lib "LIB_RK") (part "AAA-PCI-047-K01"))
    )
    (comp (ref "X17")
      (value "AAA-PCI-047-K01")
      (footprint "AAA-PCI-047-K01")
      (description "mPCI-E Surface Mount 52 SMD,P=0.8mm Card Edge Connectors")
      (fields (field (name "MANUFACTURER") "LOTES"))
      (libsource (lib "LIB_RK") (part "AAA-PCI-047-K01"))
    )
    (comp (ref "X18")
      (value "X1613WS-36-9TV01")
      (footprint "X1613WS-36-9TV01")
      (description "Clamp Plate 36P Through Hole,P=1mm Pluggable Connector Assemblies ROHS")
      (fields (field (name "MANUFACTURER") "XKB Connection"))
      (libsource (lib "LIB_RK") (part "X1613WS-36-9TV01"))
    )
    (comp (ref "X19")
      (value "X1613WS-36-9TV01")
      (footprint "X1613WS-36-9TV01")
      (description "Clamp Plate 36P Through Hole,P=1mm Pluggable Connector Assemblies ROHS")
      (fields (field (name "MANUFACTURER") "XKB Connection"))
      (libsource (lib "LIB_RK") (part "X1613WS-36-9TV01"))
    )
    (comp (ref "X39")
      (value "SMTSO2066MTJ")
      (footprint "SMTSO2066MTJ")
      (fields (field (name "MANUFACTURER") "Sinhoo"))
      (libsource (lib "LIB_RK") (part "SMTSO2066MTJ"))
    )
    (comp (ref "X40")
      (value "SMTSO2066MTJ")
      (footprint "SMTSO2066MTJ")
      (fields (field (name "MANUFACTURER") "Sinhoo"))
      (libsource (lib "LIB_RK") (part "SMTSO2066MTJ"))
    )
  )
  (nets
    (net (code "13") (name "+1.2V_PCI") (class "Default")
      (node (ref "C339") (pin "1") (pinfunction "1_1") (pintype "passive"))
      (node (ref "C340") (pin "1") (pinfunction "1_1") (pintype "passive"))
      (node (ref "C341") (pin "1") (pinfunction "1_1") (pintype "passive"))
      (node (ref "C342") (pin "1") (pinfunction "1_1") (pintype "passive"))
      (node (ref "C343") (pin "1") (pinfunction "1_1") (pintype "passive"))
      (node (ref "C344") (pin "1") (pinfunction "1_1") (pintype "passive"))
      (node (ref "C345") (pin "1") (pinfunction "1_1") (pintype "passive"))
      (node (ref "D21") (pin "15") (pinfunction "1V2_15") (pintype "power_in"))
      (node (ref "D21") (pin "17") (pinfunction "1V2_17") (pintype "power_in"))
      (node (ref "D21") (pin "20") (pinfunction "1V2_20") (pintype "power_in"))
      (node (ref "D21") (pin "26") (pinfunction "1V2_26") (pintype "power_in"))
      (node (ref "D21") (pin "29") (pinfunction "1V2_29") (pintype "power_in"))
      (node (ref "D21") (pin "37") (pinfunction "1V2_37") (pintype "power_in"))
      (node (ref "D21") (pin "43") (pinfunction "1V2_43") (pintype "power_in"))
      (node (ref "D21") (pin "48") (pinfunction "1V2_48") (pintype "power_in"))
      (node (ref "D21") (pin "50") (pinfunction "1V2_50") (pintype "power_in"))
      (node (ref "D21") (pin "61") (pinfunction "1V2_61") (pintype "power_in"))
      (node (ref "D21") (pin "64") (pinfunction "1V2_64") (pintype "power_in"))
      (node (ref "D21") (pin "9") (pinfunction "1V2_9") (pintype "power_in"))
    )
    (net (code "14") (name "+12V_VCC_DEVICE") (class "Default")
      (node (ref "R155") (pin "1") (pinfunction "1_1") (pintype "passive"))
      (node (ref "R156") (pin "1") (pinfunction "1_1") (pintype "passive"))
      (node (ref "R157") (pin "1") (pinfunction "1_1") (pintype "passive"))
      (node (ref "R158") (pin "1") (pinfunction "1_1") (pintype "passive"))
      (node (ref "VT18") (pin "1") (pinfunction "1_1") (pintype "passive"))
      (node (ref "VT18") (pin "2") (pinfunction "2_2") (pintype "passive"))
      (node (ref "VT18") (pin "3") (pinfunction "3_3") (pintype "passive"))
      (node (ref "VT19") (pin "1") (pinfunction "1_1") (pintype "passive"))
      (node (ref "VT19") (pin "2") (pinfunction "2_2") (pintype "passive"))
      (node (ref "VT19") (pin "3") (pinfunction "3_3") (pintype "passive"))
      (node (ref "VT20") (pin "1") (pinfunction "1_1") (pintype "passive"))
      (node (ref "VT20") (pin "2") (pinfunction "2_2") (pintype "passive"))
      (node (ref "VT20") (pin "3") (pinfunction "3_3") (pintype "passive"))
      (node (ref "VT21") (pin "1") (pinfunction "1_1") (pintype "passive"))
      (node (ref "VT21") (pin "2") (pinfunction "2_2") (pintype "passive"))
      (node (ref "VT21") (pin "3") (pinfunction "3_3") (pintype "passive"))
    )
    (net (code "15") (name "+12V_VCC_PCIE1") (class "Default")
      (node (ref "VT18") (pin "5") (pinfunction "5_5") (pintype "passive"))
      (node (ref "VT18") (pin "6") (pinfunction "6_6") (pintype "passive"))
      (node (ref "VT18") (pin "7") (pinfunction "7_7") (pintype "passive"))
      (node (ref "VT18") (pin "8") (pinfunction "8_8") (pintype "passive"))
      (node (ref "X18") (pin "B1") (pinfunction "+12V_B1") (pintype "passive"))
      (node (ref "X18") (pin "B2") (pinfunction "+12V_B2") (pintype "passive"))
      (node (ref "X18") (pin "B3") (pinfunction "+12V_B3") (pintype "passive"))
      (node (ref "X18") (pin "B4") (pinfunction "GND_B4") (pintype "passive"))
    )
    (net (code "16") (name "+12V_VCC_PCIE2") (class "Default")
      (node (ref "VT21") (pin "5") (pinfunction "5_5") (pintype "passive"))
      (node (ref "VT21") (pin "6") (pinfunction "6_6") (pintype "passive"))
      (node (ref "VT21") (pin "7") (pinfunction "7_7") (pintype "passive"))
      (node (ref "VT21") (pin "8") (pinfunction "8_8") (pintype "passive"))
      (node (ref "X19") (pin "B1") (pinfunction "+12V_B1") (pintype "passive"))
      (node (ref "X19") (pin "B2") (pinfunction "+12V_B2") (pintype "passive"))
      (node (ref "X19") (pin "B3") (pinfunction "+12V_B3") (pintype "passive"))
      (node (ref "X19") (pin "B4") (pinfunction "GND_B4") (pintype "passive"))
    )
    (net (code "17") (name "+12V_VCC_mPCIe3") (class "Default")
      (node (ref "VT19") (pin "5") (pinfunction "5_5") (pintype "passive"))
      (node (ref "VT19") (pin "6") (pinfunction "6_6") (pintype "passive"))
      (node (ref "VT19") (pin "7") (pinfunction "7_7") (pintype "passive"))
      (node (ref "VT19") (pin "8") (pinfunction "8_8") (pintype "passive"))
      (node (ref "X16") (pin "10") (pinfunction "UIM_DATA_10") (pintype "passive"))
      (node (ref "X16") (pin "12") (pinfunction "UIM_CLK_12") (pintype "passive"))
      (node (ref "X16") (pin "14") (pinfunction "UIM_RESET_14") (pintype "passive"))
      (node (ref "X16") (pin "16") (pinfunction "UIM_VPP_16") (pintype "passive"))
      (node (ref "X16") (pin "6") (pinfunction "1.5V_6") (pintype "passive"))
      (node (ref "X16") (pin "8") (pinfunction "UIM_PWR_8") (pintype "passive"))
    )
    (net (code "18") (name "+12V_VCC_mPCIe4") (class "Default")
      (node (ref "VT20") (pin "5") (pinfunction "5_5") (pintype "passive"))
      (node (ref "VT20") (pin "6") (pinfunction "6_6") (pintype "passive"))
      (node (ref "VT20") (pin "7") (pinfunction "7_7") (pintype "passive"))
      (node (ref "VT20") (pin "8") (pinfunction "8_8") (pintype "passive"))
      (node (ref "X17") (pin "10") (pinfunction "UIM_DATA_10") (pintype "passive"))
      (node (ref "X17") (pin "12") (pinfunction "UIM_CLK_12") (pintype "passive"))
      (node (ref "X17") (pin "14") (pinfunction "UIM_RESET_14") (pintype "passive"))
      (node (ref "X17") (pin "16") (pinfunction "UIM_VPP_16") (pintype "passive"))
      (node (ref "X17") (pin "6") (pinfunction "1.5V_6") (pintype "passive"))
      (node (ref "X17") (pin "8") (pinfunction "UIM_PWR_8") (pintype "passive"))
    )
    (net (code "19") (name "/1PCIE20_TX_N") (class "Default")
      (node (ref "C315") (pin "1") (pinfunction "1_1") (pintype "passive"))
      (node (ref "D21") (pin "12") (pinfunction "TXN_1_12") (pintype "output"))
    )
    (net (code "20") (name "/1PCIE20_TX_P") (class "Default")
      (node (ref "C314") (pin "1") (pinfunction "1_1") (pintype "passive"))
      (node (ref "D21") (pin "11") (pinfunction "TXP_1_11") (pintype "output"))
    )
    (net (code "21") (name "/2mPCIe20_TX_N") (class "Default")
      (node (ref "C308") (pin "2") (pinfunction "2_2") (pintype "passive"))
      (node (ref "X16") (pin "31") (pinfunction "PETn0_31") (pintype "passive"))
    )
    (net (code "22") (name "/2mPCIe20_TX_P") (class "Default")
      (node (ref "C309") (pin "2") (pinfunction "2_2") (pintype "passive"))
      (node (ref "X16") (pin "33") (pinfunction "РЕТр0_33") (pintype "passive"))
    )
    (net (code "23") (name "/3PCIE20_REFCLK_N") (class "Default")
      (node (ref "D21") (pin "45") (pinfunction "REFCLKN_3_45") (pintype "output"))
      (node (ref "R171") (pin "1") (pinfunction "1_1") (pintype "passive"))
      (node (ref "X18") (pin "A14") (pinfunction "REFCLK-_A14") (pintype "passive"))
    )
    (net (code "24") (name "/3PCIE20_REFCLK_P") (class "Default")
      (node (ref "D21") (pin "44") (pinfunction "REFCLKP_3_44") (pintype "output"))
      (node (ref "R170") (pin "1") (pinfunction "1_1") (pintype "passive"))
      (node (ref "X18") (pin "A13") (pinfunction "REFCLK+_A13") (pintype "passive"))
    )
    (net (code "25") (name "/3PCIE20_RX_N") (class "Default")
      (node (ref "D21") (pin "42") (pinfunction "RXN_3_42") (pintype "input"))
      (node (ref "X18") (pin "A17") (pinfunction "_PERn0_A17") (pintype "passive"))
    )
    (net (code "26") (name "/3PCIE20_RX_P") (class "Default")
      (node (ref "D21") (pin "41") (pinfunction "RXP_3_41") (pintype "input"))
      (node (ref "X18") (pin "A16") (pinfunction "_PERp0_A16") (pintype "passive"))
    )
    (net (code "27") (name "/3PCIE20_TX_N") (class "Default")
      (node (ref "C312") (pin "2") (pinfunction "2_2") (pintype "passive"))
      (node (ref "D21") (pin "40") (pinfunction "TXN_3_40") (pintype "output"))
    )
    (net (code "28") (name "/3PCIE20_TX_P") (class "Default")
      (node (ref "C310") (pin "2") (pinfunction "2_2") (pintype "passive"))
      (node (ref "D21") (pin "39") (pinfunction "TXP_3_39") (pintype "output"))
    )
    (net (code "29") (name "/3_PCIE20_TX_N") (class "Default")
      (node (ref "C312") (pin "1") (pinfunction "1_1") (pintype "passive"))
      (node (ref "X18") (pin "B15") (pinfunction "_PETn0_B15") (pintype "passive"))
    )
    (net (code "30") (name "/3_PCIE20_TX_P") (class "Default")
      (node (ref "C310") (pin "1") (pinfunction "1_1") (pintype "passive"))
      (node (ref "X18") (pin "B14") (pinfunction "PETp0_B14") (pintype "passive"))
    )
    (net (code "31") (name "/4PCIE1_20_TX_N") (class "Default")
      (node (ref "C24") (pin "2") (pinfunction "2_2") (pintype "passive"))
      (node (ref "X17") (pin "31") (pinfunction "PETn0_31") (pintype "passive"))
    )
    (net (code "32") (name "/4PCIE1_20_TX_P") (class "Default")
      (node (ref "C32") (pin "2") (pinfunction "2_2") (pintype "passive"))
      (node (ref "X17") (pin "33") (pinfunction "РЕТр0_33") (pintype "passive"))
    )
    (net (code "33") (name "/4PCIE20_REFCLK_N") (class "Default")
      (node (ref "D21") (pin "63") (pinfunction "REFCLKN_4_63") (pintype "output"))
      (node (ref "R173") (pin "1") (pinfunction "1_1") (pintype "passive"))
      (node (ref "X19") (pin "A14") (pinfunction "REFCLK-_A14") (pintype "passive"))
    )
    (net (code "34") (name "/4PCIE20_REFCLK_P") (class "Default")
      (node (ref "D21") (pin "62") (pinfunction "REFCLKP_4_62") (pintype "output"))
      (node (ref "R172") (pin "1") (pinfunction "1_1") (pintype "passive"))
      (node (ref "X19") (pin "A13") (pinfunction "REFCLK+_A13") (pintype "passive"))
    )
    (net (code "35") (name "/4PCIE20_RX_N") (class "Default")
      (node (ref "D21") (pin "60") (pinfunction "RXN_4_60") (pintype "input"))
      (node (ref "X19") (pin "A17") (pinfunction "_PERn0_A17") (pintype "passive"))
    )
    (net (code "36") (name "/4PCIE20_RX_P") (class "Default")
      (node (ref "D21") (pin "59") (pinfunction "RXP_4_59") (pintype "input"))
      (node (ref "X19") (pin "A16") (pinfunction "_PERp0_A16") (pintype "passive"))
    )
    (net (code "37") (name "/4PCIE20_TX_N") (class "Default")
      (node (ref "C313") (pin "2") (pinfunction "2_2") (pintype "passive"))
      (node (ref "D21") (pin "58") (pinfunction "TXN_4_58") (pintype "output"))
    )
    (net (code "38") (name "/4PCIE20_TX_P") (class "Default")
      (node (ref "C311") (pin "2") (pinfunction "2_2") (pintype "passive"))
      (node (ref "D21") (pin "57") (pinfunction "TXP_4_57") (pintype "output"))
    )
    (net (code "39") (name "/4_PCIE20_TX_N") (class "Default")
      (node (ref "C313") (pin "1") (pinfunction "1_1") (pintype "passive"))
      (node (ref "X19") (pin "B15") (pinfunction "_PETn0_B15") (pintype "passive"))
    )
    (net (code "40") (name "/4_PCIE20_TX_P") (class "Default")
      (node (ref "C311") (pin "1") (pinfunction "1_1") (pintype "passive"))
      (node (ref "X19") (pin "B14") (pinfunction "PETp0_B14") (pintype "passive"))
    )
    (net (code "41") (name "/ASMPCIE20_RX_N") (class "Default")
      (node (ref "C321") (pin "2") (pinfunction "2_2") (pintype "passive"))
      (node (ref "D21") (pin "55") (pinfunction "TXN_IN_55") (pintype "output"))
    )
    (net (code "42") (name "/ASMPCIE20_RX_P") (class "Default")
      (node (ref "C319") (pin "2") (pinfunction "2_2") (pintype "passive"))
      (node (ref "D21") (pin "54") (pinfunction "TXP_IN_54") (pintype "output"))
    )
    (net (code "43") (name "/ASMPCIE20_TX_N") (class "Default")
      (node (ref "D2") (pin "P28") (pinfunction "PCIE0_TXN_P28") (pintype "output"))
      (node (ref "D21") (pin "52") (pinfunction "RXN_IN_52") (pintype "input"))
    )
    (net (code "44") (name "/ASMPCIE20_TX_P") (class "Default")
      (node (ref "D2") (pin "P29") (pinfunction "PCIE0_TXP_P29") (pintype "output"))
      (node (ref "D21") (pin "51") (pinfunction "RXP_IN_51") (pintype "input"))
    )
    (net (code "45") (name "/GMAC1_MDC") (class "Default")
      (node (ref "X17") (pin "26") (pinfunction "GND_26") (pintype "passive"))
      (node (ref "X18") (pin "B8") (pinfunction "+3.3V_B8") (pintype "passive"))
    )
    (net (code "46") (name "/GMAC1_MDIO") (class "Default")
      (node (ref "X17") (pin "24") (pinfunction "+3.3Vaux_24") (pintype "passive"))
      (node (ref "X18") (pin "B9") (pinfunction "JTAG1-TRST#_B9") (pintype "passive"))
    )
    (net (code "47") (name "/HDMI{slash}EDP_TX0_N") (class "Default")
      (node (ref "D2") (pin "AK27") (pinfunction "HDMI_TX_D0N_AK27") (pintype "output"))
    )
    (net (code "48") (name "/HDMI{slash}EDP_TX0_P") (class "Default")
      (node (ref "D2") (pin "1AE24") (pinfunction "HDMI_TX_D0P_1AE24") (pintype "output"))
    )
    (net (code "49") (name "/HDMI{slash}EDP_TX1_N") (class "Default")
      (node (ref "D2") (pin "AL28") (pinfunction "HDMI_TX_D1N_AL28") (pintype "output"))
    )
    (net (code "50") (name "/HDMI{slash}EDP_TX1_P") (class "Default")
      (node (ref "D2") (pin "AK28") (pinfunction "HDMI_TX_D1P_AK28") (pintype "output"))
    )
    (net (code "51") (name "/HDMI{slash}EDP_TX2_N") (class "Default")
      (node (ref "D2") (pin "AK29") (pinfunction "HDMI_TX_D2N_AK29") (pintype "output"))
    )
    (net (code "52") (name "/HDMI{slash}EDP_TX2_P") (class "Default")
      (node (ref "D2") (pin "AJ28") (pinfunction "HDMI_TX_D2P_AJ28") (pintype "output"))
    )
    (net (code "53") (name "/HDMI{slash}EDP_TXC_N") (class "Default")
      (node (ref "D2") (pin "AK26") (pinfunction "HDMI_TX_D3N_AK26") (pintype "output"))
    )
    (net (code "54") (name "/HDMI{slash}EDP_TXC_P") (class "Default")
      (node (ref "D2") (pin "AL26") (pinfunction "HDMI_TX_D3P_AL26") (pintype "output"))
    )
    (net (code "55") (name "/HDMI{slash}EDP_TX_SBD_N") (class "Default")
      (node (ref "D2") (pin "2U12") (pinfunction "HDMI_TX_SBDN_2U12") (pintype "output"))
    )
    (net (code "56") (name "/HDMI{slash}EDP_TX_SBD_P") (class "Default")
      (node (ref "D2") (pin "2T12") (pinfunction "HDMI_TX_SBDP_2T12") (pintype "output"))
    )
    (net (code "57") (name "/I2C0_SCL") (class "Default")
      (node (ref "X16") (pin "30") (pinfunction "SMB_CLK_30") (pintype "passive"))
    )
    (net (code "58") (name "/I2C0_SDA") (class "Default")
      (node (ref "X16") (pin "32") (pinfunction "SMB_DATA_32") (pintype "passive"))
    )
    (net (code "59") (name "/I2C1_SCL") (class "Default")
      (node (ref "X17") (pin "30") (pinfunction "SMB_CLK_30") (pintype "passive"))
    )
    (net (code "60") (name "/I2C1_SDA") (class "Default")
      (node (ref "X17") (pin "32") (pinfunction "SMB_DATA_32") (pintype "passive"))
    )
    (net (code "61") (name "/MINI1PCIE20_REFCLK_N") (class "Default")
      (node (ref "D21") (pin "19") (pinfunction "REFCLKN_1_19") (pintype "output"))
    )
    (net (code "62") (name "/MINI1PCIE20_REFCLK_P") (class "Default")
      (node (ref "D21") (pin "18") (pinfunction "REFCLKP_1_18") (pintype "output"))
    )
    (net (code "63") (name "/MINI1PCIE20_RX_N") (class "Default")
      (node (ref "D21") (pin "14") (pinfunction "RXN_1_14") (pintype "input"))
    )
    (net (code "64") (name "/MINI1PCIE20_RX_P") (class "Default")
      (node (ref "D21") (pin "13") (pinfunction "RXP_1_13") (pintype "input"))
    )
    (net (code "65") (name "/MINI1PCIE20_TX_N") (class "Default")
      (node (ref "C315") (pin "2") (pinfunction "2_2") (pintype "passive"))
    )
    (net (code "66") (name "/MINI1PCIE20_TX_P") (class "Default")
      (node (ref "C314") (pin "2") (pinfunction "2_2") (pintype "passive"))
    )
    (net (code "67") (name "/MINI2PCIE20_REFCLK_N") (class "Default")
      (node (ref "D21") (pin "28") (pinfunction "REFCLKN_2_28") (pintype "output"))
      (node (ref "X16") (pin "11") (pinfunction "REFCLK-_11") (pintype "passive"))
    )
    (net (code "68") (name "/MINI2PCIE20_REFCLK_P") (class "Default")
      (node (ref "D21") (pin "27") (pinfunction "REFCLKP_2_27") (pintype "output"))
      (node (ref "X16") (pin "13") (pinfunction "REFCLK+_13") (pintype "passive"))
    )
    (net (code "69") (name "/MINI2PCIE20_RX_N") (class "Default")
      (node (ref "D21") (pin "25") (pinfunction "RXN_2_25") (pintype "input"))
      (node (ref "X16") (pin "23") (pinfunction "PERn0_23") (pintype "passive"))
    )
    (net (code "70") (name "/MINI2PCIE20_RX_P") (class "Default")
      (node (ref "D21") (pin "24") (pinfunction "RXP_2_24") (pintype "input"))
      (node (ref "X16") (pin "25") (pinfunction "PERp0_25") (pintype "passive"))
    )
    (net (code "71") (name "/MINI2PCIE20_TX_N") (class "Default")
      (node (ref "C308") (pin "1") (pinfunction "1_1") (pintype "passive"))
      (node (ref "D21") (pin "23") (pinfunction "TXN_2_23") (pintype "output"))
    )
    (net (code "72") (name "/MINI2PCIE20_TX_P") (class "Default")
      (node (ref "C309") (pin "1") (pinfunction "1_1") (pintype "passive"))
      (node (ref "D21") (pin "22") (pinfunction "TXP_2_22") (pintype "output"))
    )
    (net (code "73") (name "/PCIE1_20_REFCLK_N") (class "Default")
      (node (ref "D2") (pin "1M23") (pinfunction "PCIE1_REFCLKN_1M23") (pintype "output"))
      (node (ref "X17") (pin "11") (pinfunction "REFCLK-_11") (pintype "passive"))
    )
    (net (code "74") (name "/PCIE1_20_REFCLK_P") (class "Default")
      (node (ref "D2") (pin "1L23") (pinfunction "PCIE1_REFCLKP_1L23") (pintype "output"))
      (node (ref "X17") (pin "13") (pinfunction "REFCLK+_13") (pintype "passive"))
    )
    (net (code "75") (name "/PCIE1_20_RX_N") (class "Default")
      (node (ref "D2") (pin "M29") (pinfunction "PCIE1_RXN_M29") (pintype "input"))
      (node (ref "X17") (pin "23") (pinfunction "PERn0_23") (pintype "passive"))
    )
    (net (code "76") (name "/PCIE1_20_RX_P") (class "Default")
      (node (ref "D2") (pin "M28") (pinfunction "PCIE1_RXP_M28") (pintype "input"))
      (node (ref "X17") (pin "25") (pinfunction "PERp0_25") (pintype "passive"))
    )
    (net (code "77") (name "/PCIE1_20_TX_N") (class "Default")
      (node (ref "C24") (pin "1") (pinfunction "1_1") (pintype "passive"))
      (node (ref "D2") (pin "N29") (pinfunction "PCIE1_TXN_N29") (pintype "output"))
    )
    (net (code "78") (name "/PCIE1_20_TX_P") (class "Default")
      (node (ref "C32") (pin "1") (pinfunction "1_1") (pintype "passive"))
      (node (ref "D2") (pin "N28") (pinfunction "PCIE1_TXP_N28") (pintype "output"))
    )
    (net (code "79") (name "/PCIE1_PWR_ON") (class "Default")
      (node (ref "R159") (pin "1") (pinfunction "1_1") (pintype "passive"))
    )
    (net (code "80") (name "/PCIE2_PWR_ON") (class "Default")
      (node (ref "R162") (pin "1") (pinfunction "1_1") (pintype "passive"))
    )
    (net (code "81") (name "/PCIE20_PERSTn") (class "Default")
      (node (ref "D21") (pin "3") (pinfunction "RES_IN_3") (pintype "input"))
    )
    (net (code "82") (name "/PCIE20_REFCLK_N") (class "Default")
      (node (ref "D2") (pin "1N23") (pinfunction "PCIE0_REFCLKN_1N23") (pintype "output"))
      (node (ref "D21") (pin "47") (pinfunction "REFCLKN_IN_47") (pintype "input"))
    )
    (net (code "83") (name "/PCIE20_REFCLK_P") (class "Default")
      (node (ref "D2") (pin "1N22") (pinfunction "PCIE0_REFCLKP_1N22") (pintype "output"))
      (node (ref "D21") (pin "46") (pinfunction "REFCLKP_IN_46") (pintype "input"))
    )
    (net (code "84") (name "/PCIE20_RX_N") (class "Default")
      (node (ref "C321") (pin "1") (pinfunction "1_1") (pintype "passive"))
      (node (ref "D2") (pin "R29") (pinfunction "PCIE0_RXN_R29") (pintype "input"))
    )
    (net (code "85") (name "/PCIE20_RX_P") (class "Default")
      (node (ref "C319") (pin "1") (pinfunction "1_1") (pintype "passive"))
      (node (ref "D2") (pin "R28") (pinfunction "PCIE0_RXP_R28") (pintype "input"))
    )
    (net (code "86") (name "/PCIE_GMAC1_RXCLK") (class "Default")
      (node (ref "X18") (pin "A7") (pinfunction "JTAG4-TDO_A7") (pintype "passive"))
    )
    (net (code "87") (name "/PCIE_GMAC1_RXCTL") (class "Default")
      (node (ref "X18") (pin "A9") (pinfunction "+3.3V_A9") (pintype "passive"))
    )
    (net (code "88") (name "/PCIE_GMAC1_RXD0") (class "Default")
      (node (ref "X18") (pin "A8") (pinfunction "JTAG5-TMS_A8") (pintype "passive"))
    )
    (net (code "89") (name "/PCIE_GMAC1_RXD1") (class "Default")
      (node (ref "X18") (pin "A11") (pinfunction "PWRGD/PERST_A11") (pintype "passive"))
    )
    (net (code "90") (name "/PCIE_GMAC1_RXD2") (class "Default")
      (node (ref "X18") (pin "A12") (pinfunction "GND_A12") (pintype "passive"))
    )
    (net (code "91") (name "/PCIE_GMAC1_RXD3") (class "Default")
      (node (ref "X18") (pin "A10") (pinfunction "+3.3V_A10") (pintype "passive"))
    )
    (net (code "92") (name "/PCIE_GMAC1_TXCLK") (class "Default")
      (node (ref "X18") (pin "A6") (pinfunction "JTAG3-TDI_A6") (pintype "passive"))
    )
    (net (code "93") (name "/PCIE_GMAC1_TXCTL") (class "Default")
      (node (ref "X18") (pin "A1") (pinfunction "PRSNT1#_A1") (pintype "passive"))
    )
    (net (code "94") (name "/PCIE_GMAC1_TXD0") (class "Default")
      (node (ref "X18") (pin "A5") (pinfunction "JTAG2-TCK_A5") (pintype "passive"))
    )
    (net (code "95") (name "/PCIE_GMAC1_TXD1") (class "Default")
      (node (ref "X18") (pin "A4") (pinfunction "GND_A4") (pintype "passive"))
    )
    (net (code "96") (name "/PCIE_GMAC1_TXD2") (class "Default")
      (node (ref "X18") (pin "A3") (pinfunction "+12V_A3") (pintype "passive"))
    )
    (net (code "97") (name "/PCIE_GMAC1_TXD3") (class "Default")
      (node (ref "X18") (pin "A2") (pinfunction "+12V_A2") (pintype "passive"))
    )
    (net (code "98") (name "/PCIe1_Detect") (class "Default")
      (node (ref "X18") (pin "B11") (pinfunction "WAKE#_B11") (pintype "passive"))
    )
    (net (code "99") (name "/PCIe2_Detect") (class "Default")
      (node (ref "X19") (pin "B11") (pinfunction "WAKE#_B11") (pintype "passive"))
    )
    (net (code "100") (name "/PERST#") (class "Default")
      (node (ref "D21") (pin "2") (pinfunction "RES_OUT_2") (pintype "output"))
      (node (ref "X16") (pin "22") (pinfunction "PERST#_22") (pintype "passive"))
      (node (ref "X17") (pin "22") (pinfunction "PERST#_22") (pintype "passive"))
      (node (ref "X18") (pin "B7") (pinfunction "GND_B7") (pintype "passive"))
      (node (ref "X19") (pin "A11") (pinfunction "PWRGD/PERST_A11") (pintype "passive"))
    )
    (net (code "101") (name "/PHY1_RSTn") (class "Default")
      (node (ref "X17") (pin "20") (pinfunction "W_DISABLE#_20") (pintype "passive"))
      (node (ref "X18") (pin "B10") (pinfunction "+3.3V-AUX_B10") (pintype "passive"))
    )
    (net (code "102") (name "/RK_ASM_I2C_SCL") (class "Default")
      (node (ref "X19") (pin "A2") (pinfunction "+12V_A2") (pintype "passive"))
    )
    (net (code "103") (name "/RK_ASM_I2C_SDA") (class "Default")
      (node (ref "X19") (pin "A3") (pinfunction "+12V_A3") (pintype "passive"))
    )
    (net (code "104") (name "/UART0_RX_M0_PCIE1") (class "Default")
      (node (ref "X18") (pin "B13") (pinfunction "GND_B13") (pintype "passive"))
    )
    (net (code "105") (name "/UART0_RX_M0_PCIE2") (class "Default")
      (node (ref "X19") (pin "B13") (pinfunction "GND_B13") (pintype "passive"))
    )
    (net (code "106") (name "/UART0_RX_M0_mPCIe") (class "Default")
      (node (ref "X16") (pin "3") (pinfunction "СОЕХ1_3") (pintype "passive"))
    )
    (net (code "107") (name "/UART0_TX_M0_PCIE1") (class "Default")
      (node (ref "X18") (pin "B12") (pinfunction "RSVD_B12") (pintype "passive"))
    )
    (net (code "108") (name "/UART0_TX_M0_PCIE2") (class "Default")
      (node (ref "X19") (pin "B12") (pinfunction "RSVD_B12") (pintype "passive"))
    )
    (net (code "109") (name "/UART0_TX_M0_mPCIe") (class "Default")
      (node (ref "X16") (pin "1") (pinfunction "WAKE#_1") (pintype "passive"))
    )
    (net (code "110") (name "/USB1_PCIE1_D_N") (class "Default")
      (node (ref "D42") (pin "4") (pinfunction "M-_4") (pintype "passive"))
      (node (ref "X18") (pin "B6") (pinfunction "SMDAT_B6") (pintype "passive"))
    )
    (net (code "111") (name "/USB1_PCIE1_D_P") (class "Default")
      (node (ref "D42") (pin "5") (pinfunction "M+_5") (pintype "passive"))
      (node (ref "X18") (pin "B5") (pinfunction "_SMCLK_B5") (pintype "passive"))
    )
    (net (code "112") (name "/USB2_HOST1_D_N") (class "Default")
      (node (ref "D2") (pin "2T5") (pinfunction "USB2_OTG1_DM_2T5") (pintype "bidirectional"))
    )
    (net (code "113") (name "/USB2_HOST1_D_P") (class "Default")
      (node (ref "D2") (pin "2T4") (pinfunction "USB2_OTG1_DP_2T4") (pintype "bidirectional"))
    )
    (net (code "114") (name "/USB2_OTG0_D_N") (class "Default")
      (node (ref "D2") (pin "AL9") (pinfunction "USB2_OTG0_DM_AL9") (pintype "bidirectional"))
    )
    (net (code "115") (name "/USB2_OTG0_D_P") (class "Default")
      (node (ref "D2") (pin "AK9") (pinfunction "USB2_OTG0_DP_AK9") (pintype "bidirectional"))
    )
    (net (code "116") (name "/USB2_OTG0_ID") (class "Default")
      (node (ref "D2") (pin "2R6") (pinfunction "USB2_OTG0_ID_2R6") (pintype "passive"))
      (node (ref "R167") (pin "2") (pinfunction "2_2") (pintype "passive"))
    )
    (net (code "117") (name "/USB2_OTG0_VBUSDET") (class "Default")
      (node (ref "D2") (pin "2P3") (pinfunction "USB2_OTG0_VBUSDET_2P3") (pintype "passive"))
    )
    (net (code "118") (name "/USB2_mPCIe3_D_N") (class "Default")
      (node (ref "D42") (pin "6") (pinfunction "D-_6") (pintype "passive"))
      (node (ref "X17") (pin "36") (pinfunction "USB_D-_36") (pintype "passive"))
    )
    (net (code "119") (name "/USB2_mPCIe3_D_P") (class "Default")
      (node (ref "D42") (pin "7") (pinfunction "D+_7") (pintype "passive"))
      (node (ref "X17") (pin "38") (pinfunction "USB_D+_38") (pintype "passive"))
    )
    (net (code "120") (name "/USB3_OTG0_SS_RX1_N") (class "Default")
      (node (ref "D2") (pin "AL10") (pinfunction "USB3_OTG0_SSRX1N_AL10") (pintype "bidirectional"))
    )
    (net (code "121") (name "/USB3_OTG0_SS_RX1_P") (class "Default")
      (node (ref "D2") (pin "AK10") (pinfunction "USB3_OTG0_SSRX1P_AK10") (pintype "bidirectional"))
    )
    (net (code "122") (name "/USB3_OTG0_SS_TX1_N") (class "Default")
      (node (ref "D2") (pin "AK11") (pinfunction "USB3_OTG0_SSTX1N_AK11") (pintype "output"))
    )
    (net (code "123") (name "/USB3_OTG0_SS_TX1_P") (class "Default")
      (node (ref "D2") (pin "AL11") (pinfunction "USB3_OTG0_SSTX1P_AL11") (pintype "output"))
    )
    (net (code "124") (name "/USB_PCIE1_D_N") (class "Default")
      (node (ref "D42") (pin "2") (pinfunction "Y-_2") (pintype "passive"))
    )
    (net (code "125") (name "/USB_PCIE1_D_P") (class "Default")
      (node (ref "D42") (pin "1") (pinfunction "Y+_1") (pintype "passive"))
    )
    (net (code "126") (name "/USB_PCIE2_D_N") (class "Default")
      (node (ref "X19") (pin "B5") (pinfunction "_SMCLK_B5") (pintype "passive"))
    )
    (net (code "127") (name "/USB_PCIE2_D_P") (class "Default")
      (node (ref "X19") (pin "B6") (pinfunction "SMDAT_B6") (pintype "passive"))
    )
    (net (code "128") (name "/USB_SEL") (class "Default")
      (node (ref "D42") (pin "10") (pinfunction "SEL_10") (pintype "passive"))
      (node (ref "R438") (pin "1") (pinfunction "1_1") (pintype "passive"))
    )
    (net (code "129") (name "/mPCIE_GMAC1_RXCLK") (class "Default")
      (node (ref "X17") (pin "46") (pinfunction "LED_WPAN#_46") (pintype "passive"))
    )
    (net (code "130") (name "/mPCIE_GMAC1_RXCTL") (class "Default")
      (node (ref "X17") (pin "41") (pinfunction "+3.3Vaux_41") (pintype "passive"))
    )
    (net (code "131") (name "/mPCIE_GMAC1_RXD0") (class "Default")
      (node (ref "X17") (pin "48") (pinfunction "+1.5V_48") (pintype "passive"))
    )
    (net (code "132") (name "/mPCIE_GMAC1_RXD1") (class "Default")
      (node (ref "X17") (pin "50") (pinfunction "GND_50") (pintype "passive"))
    )
    (net (code "133") (name "/mPCIE_GMAC1_RXD2") (class "Default")
      (node (ref "X17") (pin "52") (pinfunction "+3.3Vaux_52") (pintype "passive"))
    )
    (net (code "134") (name "/mPCIE_GMAC1_RXD3") (class "Default")
      (node (ref "X17") (pin "43") (pinfunction "GND_43") (pintype "passive"))
    )
    (net (code "135") (name "/mPCIE_GMAC1_TXCLK") (class "Default")
      (node (ref "X17") (pin "44") (pinfunction "LED_WLAN#_44") (pintype "passive"))
    )
    (net (code "136") (name "/mPCIE_GMAC1_TXCTL") (class "Default")
      (node (ref "X17") (pin "45") (pinfunction "Reserved_45") (pintype "passive"))
    )
    (net (code "137") (name "/mPCIE_GMAC1_TXD0") (class "Default")
      (node (ref "X17") (pin "42") (pinfunction "LED_WWAN#_42") (pintype "passive"))
    )
    (net (code "138") (name "/mPCIE_GMAC1_TXD1") (class "Default")
      (node (ref "X17") (pin "51") (pinfunction "Reserved_51") (pintype "passive"))
    )
    (net (code "139") (name "/mPCIE_GMAC1_TXD2") (class "Default")
      (node (ref "X17") (pin "49") (pinfunction "Reserved_49") (pintype "passive"))
    )
    (net (code "140") (name "/mPCIE_GMAC1_TXD3") (class "Default")
      (node (ref "X17") (pin "47") (pinfunction "Reserved_47") (pintype "passive"))
    )
    (net (code "141") (name "/mPCIe3_Detect") (class "Default")
      (node (ref "X16") (pin "48") (pinfunction "+1.5V_48") (pintype "passive"))
    )
    (net (code "142") (name "/mPCIe3_PWR_ON") (class "Default")
      (node (ref "R160") (pin "1") (pinfunction "1_1") (pintype "passive"))
    )
    (net (code "143") (name "/mPCIe4_Detect") (class "Default")
      (node (ref "X17") (pin "28") (pinfunction "+1.5V_28") (pintype "passive"))
    )
    (net (code "144") (name "/mPCIe4_PWR_ON") (class "Default")
      (node (ref "R161") (pin "1") (pinfunction "1_1") (pintype "passive"))
    )
    (net (code "159") (name "3.3V_VCC_DEVICE") (class "Default")
      (node (ref "C329") (pin "1") (pinfunction "1_1") (pintype "passive"))
      (node (ref "C330") (pin "1") (pinfunction "1_1") (pintype "passive"))
      (node (ref "C331") (pin "1") (pinfunction "1_1") (pintype "passive"))
      (node (ref "C332") (pin "1") (pinfunction "1_1") (pintype "passive"))
      (node (ref "C333") (pin "1") (pinfunction "1_1") (pintype "passive"))
      (node (ref "C334") (pin "1") (pinfunction "1_1") (pintype "passive"))
      (node (ref "C335") (pin "1") (pinfunction "1_1") (pintype "passive"))
      (node (ref "D21") (pin "1") (pinfunction "3V_AUX_1") (pintype "power_in"))
      (node (ref "D21") (pin "10") (pinfunction "3V3_10") (pintype "power_in"))
      (node (ref "D21") (pin "21") (pinfunction "3V3_21") (pintype "power_in"))
      (node (ref "D21") (pin "32") (pinfunction "3V3_32") (pintype "power_in"))
      (node (ref "D21") (pin "38") (pinfunction "3V3_38") (pintype "power_in"))
      (node (ref "D21") (pin "56") (pinfunction "3V3_56") (pintype "power_in"))
      (node (ref "R176") (pin "1") (pinfunction "1_1") (pintype "passive"))
      (node (ref "R177") (pin "1") (pinfunction "1_1") (pintype "passive"))
      (node (ref "R178") (pin "1") (pinfunction "1_1") (pintype "passive"))
      (node (ref "R179") (pin "1") (pinfunction "1_1") (pintype "passive"))
      (node (ref "R180") (pin "1") (pinfunction "1_1") (pintype "passive"))
      (node (ref "R234") (pin "2") (pinfunction "2_2") (pintype "passive"))
      (node (ref "R486") (pin "2") (pinfunction "2_2") (pintype "passive"))
      (node (ref "R487") (pin "2") (pinfunction "2_2") (pintype "passive"))
      (node (ref "R503") (pin "2") (pinfunction "2_2") (pintype "passive"))
    )
    (net (code "160") (name "GND") (class "Default")
      (node (ref "C316") (pin "2") (pinfunction "2_2") (pintype "passive"))
      (node (ref "C317") (pin "2") (pinfunction "2_2") (pintype "passive"))
      (node (ref "C318") (pin "1") (pinfunction "1_1") (pintype "passive"))
      (node (ref "C320") (pin "1") (pinfunction "1_1") (pintype "passive"))
      (node (ref "C322") (pin "1") (pinfunction "1_1") (pintype "passive"))
      (node (ref "C323") (pin "1") (pinfunction "1_1") (pintype "passive"))
      (node (ref "C324") (pin "1") (pinfunction "1_1") (pintype "passive"))
      (node (ref "C325") (pin "1") (pinfunction "1_1") (pintype "passive"))
      (node (ref "C326") (pin "1") (pinfunction "1_1") (pintype "passive"))
      (node (ref "C327") (pin "1") (pinfunction "1_1") (pintype "passive"))
      (node (ref "C328") (pin "2") (pinfunction "2_2") (pintype "passive"))
      (node (ref "C329") (pin "2") (pinfunction "2_2") (pintype "passive"))
      (node (ref "C330") (pin "2") (pinfunction "2_2") (pintype "passive"))
      (node (ref "C331") (pin "2") (pinfunction "2_2") (pintype "passive"))
      (node (ref "C332") (pin "2") (pinfunction "2_2") (pintype "passive"))
      (node (ref "C333") (pin "2") (pinfunction "2_2") (pintype "passive"))
      (node (ref "C334") (pin "2") (pinfunction "2_2") (pintype "passive"))
      (node (ref "C335") (pin "2") (pinfunction "2_2") (pintype "passive"))
      (node (ref "C336") (pin "1") (pinfunction "1_1") (pintype "passive"))
      (node (ref "C337") (pin "2") (pinfunction "2_2") (pintype "passive"))
      (node (ref "C338") (pin "1") (pinfunction "1_1") (pintype "passive"))
      (node (ref "C339") (pin "2") (pinfunction "2_2") (pintype "passive"))
      (node (ref "C340") (pin "2") (pinfunction "2_2") (pintype "passive"))
      (node (ref "C341") (pin "2") (pinfunction "2_2") (pintype "passive"))
      (node (ref "C342") (pin "2") (pinfunction "2_2") (pintype "passive"))
      (node (ref "C343") (pin "2") (pinfunction "2_2") (pintype "passive"))
      (node (ref "C344") (pin "2") (pinfunction "2_2") (pintype "passive"))
      (node (ref "C345") (pin "2") (pinfunction "2_2") (pintype "passive"))
      (node (ref "C585") (pin "1") (pinfunction "1_1") (pintype "passive"))
      (node (ref "D21") (pin "53") (pinfunction "GND_53") (pintype "power_in"))
      (node (ref "D21") (pin "PAD") (pinfunction "PAD_PAD") (pintype "passive"))
      (node (ref "D42") (pin "3") (pinfunction "GND_3") (pintype "passive"))
      (node (ref "R163") (pin "2") (pinfunction "2_2") (pintype "passive"))
      (node (ref "R164") (pin "2") (pinfunction "2_2") (pintype "passive"))
      (node (ref "R165") (pin "2") (pinfunction "2_2") (pintype "passive"))
      (node (ref "R166") (pin "2") (pinfunction "2_2") (pintype "passive"))
      (node (ref "R168") (pin "1") (pinfunction "1_1") (pintype "passive"))
      (node (ref "R169") (pin "1") (pinfunction "1_1") (pintype "passive"))
      (node (ref "R170") (pin "2") (pinfunction "2_2") (pintype "passive"))
      (node (ref "R171") (pin "2") (pinfunction "2_2") (pintype "passive"))
      (node (ref "R172") (pin "2") (pinfunction "2_2") (pintype "passive"))
      (node (ref "R173") (pin "2") (pinfunction "2_2") (pintype "passive"))
      (node (ref "R174") (pin "1") (pinfunction "1_1") (pintype "passive"))
      (node (ref "R175") (pin "2") (pinfunction "2_2") (pintype "passive"))
      (node (ref "R181") (pin "2") (pinfunction "2_2") (pintype "passive"))
      (node (ref "R182") (pin "2") (pinfunction "2_2") (pintype "passive"))
      (node (ref "R183") (pin "2") (pinfunction "2_2") (pintype "passive"))
      (node (ref "R184") (pin "2") (pinfunction "2_2") (pintype "passive"))
      (node (ref "R185") (pin "2") (pinfunction "2_2") (pintype "passive"))
      (node (ref "R186") (pin "2") (pinfunction "2_2") (pintype "passive"))
      (node (ref "R187") (pin "2") (pinfunction "2_2") (pintype "passive"))
      (node (ref "R188") (pin "2") (pinfunction "2_2") (pintype "passive"))
      (node (ref "R190") (pin "2") (pinfunction "2_2") (pintype "passive"))
      (node (ref "R192") (pin "2") (pinfunction "2_2") (pintype "passive"))
      (node (ref "R193") (pin "1") (pinfunction "1_1") (pintype "passive"))
      (node (ref "R477") (pin "2") (pinfunction "2_2") (pintype "passive"))
      (node (ref "VT22") (pin "2") (pinfunction "E_2") (pintype "passive"))
      (node (ref "VT23") (pin "2") (pinfunction "E_2") (pintype "passive"))
      (node (ref "VT24") (pin "2") (pinfunction "E_2") (pintype "passive"))
      (node (ref "VT25") (pin "2") (pinfunction "E_2") (pintype "passive"))
      (node (ref "X16") (pin "26") (pinfunction "GND_26") (pintype "passive"))
      (node (ref "X16") (pin "27") (pinfunction "GND_27") (pintype "passive"))
      (node (ref "X16") (pin "29") (pinfunction "GND_29") (pintype "passive"))
      (node (ref "X16") (pin "34") (pinfunction "GND_34") (pintype "passive"))
      (node (ref "X16") (pin "35") (pinfunction "GND_35") (pintype "passive"))
      (node (ref "X16") (pin "37") (pinfunction "GND_37") (pintype "passive"))
      (node (ref "X16") (pin "40") (pinfunction "GND_40") (pintype "passive"))
      (node (ref "X16") (pin "43") (pinfunction "GND_43") (pintype "passive"))
      (node (ref "X16") (pin "50") (pinfunction "GND_50") (pintype "passive"))
      (node (ref "X16") (pin "SH1") (pinfunction "SHIELD_SH1") (pintype "passive"))
      (node (ref "X16") (pin "SH2") (pinfunction "SHIELD_SH2") (pintype "passive"))
      (node (ref "X17") (pin "15") (pinfunction "GND_15") (pintype "passive"))
      (node (ref "X17") (pin "17") (pinfunction "Reserved_17") (pintype "passive"))
      (node (ref "X17") (pin "18") (pinfunction "GND_18") (pintype "passive"))
      (node (ref "X17") (pin "19") (pinfunction "Reserved_19") (pintype "passive"))
      (node (ref "X17") (pin "21") (pinfunction "GND_21") (pintype "passive"))
      (node (ref "X17") (pin "27") (pinfunction "GND_27") (pintype "passive"))
      (node (ref "X17") (pin "29") (pinfunction "GND_29") (pintype "passive"))
      (node (ref "X17") (pin "34") (pinfunction "GND_34") (pintype "passive"))
      (node (ref "X17") (pin "35") (pinfunction "GND_35") (pintype "passive"))
      (node (ref "X17") (pin "37") (pinfunction "GND_37") (pintype "passive"))
      (node (ref "X17") (pin "39") (pinfunction "+3.3Vaux_39") (pintype "passive"))
      (node (ref "X17") (pin "4") (pinfunction "GND_4") (pintype "passive"))
      (node (ref "X17") (pin "40") (pinfunction "GND_40") (pintype "passive"))
      (node (ref "X17") (pin "9") (pinfunction "GND_9") (pintype "passive"))
      (node (ref "X17") (pin "SH1") (pinfunction "SHIELD_SH1") (pintype "passive"))
      (node (ref "X17") (pin "SH2") (pinfunction "SHIELD_SH2") (pintype "passive"))
      (node (ref "X18") (pin "A18") (pinfunction "GND_A18") (pintype "passive"))
      (node (ref "X18") (pin "B16") (pinfunction "GND_B16") (pintype "passive"))
      (node (ref "X18") (pin "B17") (pinfunction "PRSNT#2_B17") (pintype "passive"))
      (node (ref "X18") (pin "B18") (pinfunction "GND_B18") (pintype "passive"))
      (node (ref "X19") (pin "A18") (pinfunction "GND_A18") (pintype "passive"))
      (node (ref "X19") (pin "B16") (pinfunction "GND_B16") (pintype "passive"))
      (node (ref "X19") (pin "B17") (pinfunction "PRSNT#2_B17") (pintype "passive"))
      (node (ref "X19") (pin "B18") (pinfunction "GND_B18") (pintype "passive"))
      (node (ref "X39") (pin "1") (pinfunction "1_1") (pintype "passive"))
      (node (ref "X40") (pin "1") (pinfunction "1_1") (pintype "passive"))
    )
    (net (code "161") (name "Net-(D2E-HDMI_TX_REXT{slash}EDP_TX_REXT)") (class "Default")
      (node (ref "D2") (pin "1AA20") (pinfunction "HDMI_TX_REXT/EDP_TX_REXT_1AA20") (pintype "passive"))
      (node (ref "R175") (pin "1") (pinfunction "1_1") (pintype "passive"))
    )
    (net (code "162") (name "Net-(D2E-USB2_OTG0_REXT)") (class "Default")
      (node (ref "D2") (pin "2R3") (pinfunction "USB2_OTG0_REXT_2R3") (pintype "passive"))
      (node (ref "R168") (pin "2") (pinfunction "2_2") (pintype "passive"))
    )
    (net (code "163") (name "Net-(D2E-USB2_OTG1_REXT)") (class "Default")
      (node (ref "D2") (pin "2U8") (pinfunction "USB2_OTG1_REXT_2U8") (pintype "passive"))
      (node (ref "R169") (pin "2") (pinfunction "2_2") (pintype "passive"))
    )
    (net (code "164") (name "Net-(D2E-USB3_OTG0_REXT{slash}DP_TX_REXT)") (class "Default")
      (node (ref "D2") (pin "2T7") (pinfunction "USB3_OTG0_REXT/DP_TX_REXT_2T7") (pintype "power_in"))
      (node (ref "R174") (pin "2") (pinfunction "2_2") (pintype "passive"))
    )
    (net (code "165") (name "Net-(D21B-GPIO0)") (class "Default")
      (node (ref "D21") (pin "4") (pinfunction "GPIO0_4") (pintype "power_in"))
      (node (ref "R176") (pin "2") (pinfunction "2_2") (pintype "passive"))
      (node (ref "R184") (pin "1") (pinfunction "1_1") (pintype "passive"))
    )
    (net (code "166") (name "Net-(D21B-GPIO1)") (class "Default")
      (node (ref "D21") (pin "31") (pinfunction "GPIO1_31") (pintype "power_in"))
      (node (ref "R177") (pin "2") (pinfunction "2_2") (pintype "passive"))
      (node (ref "R185") (pin "1") (pinfunction "1_1") (pintype "passive"))
    )
    (net (code "167") (name "Net-(D21B-GPIO2)") (class "Default")
      (node (ref "D21") (pin "5") (pinfunction "GPIO2_5") (pintype "power_in"))
      (node (ref "R183") (pin "1") (pinfunction "1_1") (pintype "passive"))
    )
    (net (code "168") (name "Net-(D21B-GPIO3)") (class "Default")
      (node (ref "D21") (pin "34") (pinfunction "GPIO3_34") (pintype "power_in"))
      (node (ref "R178") (pin "2") (pinfunction "2_2") (pintype "passive"))
      (node (ref "R186") (pin "1") (pinfunction "1_1") (pintype "passive"))
    )
    (net (code "169") (name "Net-(D21B-GPIO4)") (class "Default")
      (node (ref "D21") (pin "8") (pinfunction "GPIO4_8") (pintype "power_in"))
      (node (ref "R182") (pin "1") (pinfunction "1_1") (pintype "passive"))
    )
    (net (code "170") (name "Net-(D21B-GPIO5)") (class "Default")
      (node (ref "D21") (pin "30") (pinfunction "GPIO5_30") (pintype "power_in"))
      (node (ref "R179") (pin "2") (pinfunction "2_2") (pintype "passive"))
      (node (ref "R187") (pin "1") (pinfunction "1_1") (pintype "passive"))
    )
    (net (code "171") (name "Net-(D21B-GPIO6)") (class "Default")
      (node (ref "D21") (pin "35") (pinfunction "GPIO6_35") (pintype "power_in"))
      (node (ref "R181") (pin "1") (pinfunction "1_1") (pintype "passive"))
    )
    (net (code "172") (name "Net-(D21B-GPIO7)") (class "Default")
      (node (ref "D21") (pin "36") (pinfunction "GPIO7_36") (pintype "power_in"))
      (node (ref "R180") (pin "2") (pinfunction "2_2") (pintype "passive"))
      (node (ref "R188") (pin "1") (pinfunction "1_1") (pintype "passive"))
    )
    (net (code "173") (name "Net-(D21B-REXT1)") (class "Default")
      (node (ref "D21") (pin "16") (pinfunction "REXT1_16") (pintype "power_in"))
      (node (ref "R190") (pin "1") (pinfunction "1_1") (pintype "passive"))
    )
    (net (code "174") (name "Net-(D21B-REXT2)") (class "Default")
      (node (ref "D21") (pin "49") (pinfunction "REXT2_49") (pintype "power_in"))
      (node (ref "R192") (pin "1") (pinfunction "1_1") (pintype "passive"))
    )
    (net (code "175") (name "Net-(D21B-TEST_EN)") (class "Default")
      (node (ref "D21") (pin "33") (pinfunction "TEST_EN_33") (pintype "power_in"))
      (node (ref "R193") (pin "2") (pinfunction "2_2") (pintype "passive"))
    )
    (net (code "176") (name "Net-(D42-~{OE})") (class "Default")
      (node (ref "D42") (pin "8") (pinfunction "~{OE}_8") (pintype "passive"))
      (node (ref "R477") (pin "1") (pinfunction "1_1") (pintype "passive"))
    )
    (net (code "177") (name "Net-(VT22-B)") (class "Default")
      (node (ref "R159") (pin "2") (pinfunction "2_2") (pintype "passive"))
      (node (ref "R163") (pin "1") (pinfunction "1_1") (pintype "passive"))
      (node (ref "R234") (pin "1") (pinfunction "1_1") (pintype "passive"))
      (node (ref "VT22") (pin "1") (pinfunction "B_1") (pintype "passive"))
    )
    (net (code "178") (name "Net-(VT22-C)") (class "Default")
      (node (ref "R155") (pin "2") (pinfunction "2_2") (pintype "passive"))
      (node (ref "VT18") (pin "4") (pinfunction "4_4") (pintype "passive"))
      (node (ref "VT22") (pin "3") (pinfunction "C_3") (pintype "passive"))
    )
    (net (code "179") (name "Net-(VT23-B)") (class "Default")
      (node (ref "R160") (pin "2") (pinfunction "2_2") (pintype "passive"))
      (node (ref "R164") (pin "1") (pinfunction "1_1") (pintype "passive"))
      (node (ref "R486") (pin "1") (pinfunction "1_1") (pintype "passive"))
      (node (ref "VT23") (pin "1") (pinfunction "B_1") (pintype "passive"))
    )
    (net (code "180") (name "Net-(VT23-C)") (class "Default")
      (node (ref "R156") (pin "2") (pinfunction "2_2") (pintype "passive"))
      (node (ref "VT19") (pin "4") (pinfunction "4_4") (pintype "passive"))
      (node (ref "VT23") (pin "3") (pinfunction "C_3") (pintype "passive"))
    )
    (net (code "181") (name "Net-(VT24-B)") (class "Default")
      (node (ref "R161") (pin "2") (pinfunction "2_2") (pintype "passive"))
      (node (ref "R165") (pin "1") (pinfunction "1_1") (pintype "passive"))
      (node (ref "R487") (pin "1") (pinfunction "1_1") (pintype "passive"))
      (node (ref "VT24") (pin "1") (pinfunction "B_1") (pintype "passive"))
    )
    (net (code "182") (name "Net-(VT24-C)") (class "Default")
      (node (ref "R157") (pin "2") (pinfunction "2_2") (pintype "passive"))
      (node (ref "VT20") (pin "4") (pinfunction "4_4") (pintype "passive"))
      (node (ref "VT24") (pin "3") (pinfunction "C_3") (pintype "passive"))
    )
    (net (code "183") (name "Net-(VT25-B)") (class "Default")
      (node (ref "R162") (pin "2") (pinfunction "2_2") (pintype "passive"))
      (node (ref "R166") (pin "1") (pinfunction "1_1") (pintype "passive"))
      (node (ref "R503") (pin "1") (pinfunction "1_1") (pintype "passive"))
      (node (ref "VT25") (pin "1") (pinfunction "B_1") (pintype "passive"))
    )
    (net (code "184") (name "Net-(VT25-C)") (class "Default")
      (node (ref "R158") (pin "2") (pinfunction "2_2") (pintype "passive"))
      (node (ref "VT21") (pin "4") (pinfunction "4_4") (pintype "passive"))
      (node (ref "VT25") (pin "3") (pinfunction "C_3") (pintype "passive"))
    )
    (net (code "185") (name "VCC5V0_DEVICE_S0") (class "Default")
      (node (ref "C585") (pin "2") (pinfunction "2_2") (pintype "passive"))
      (node (ref "D42") (pin "9") (pinfunction "VDD_9") (pintype "passive"))
      (node (ref "R438") (pin "2") (pinfunction "2_2") (pintype "passive"))
    )
    (net (code "186") (name "VCCA_1V8_S0") (class "Default")
      (node (ref "C317") (pin "1") (pinfunction "1_1") (pintype "passive"))
      (node (ref "C318") (pin "2") (pinfunction "2_2") (pintype "passive"))
      (node (ref "C322") (pin "2") (pinfunction "2_2") (pintype "passive"))
      (node (ref "C325") (pin "2") (pinfunction "2_2") (pintype "passive"))
      (node (ref "C336") (pin "2") (pinfunction "2_2") (pintype "passive"))
      (node (ref "C337") (pin "1") (pinfunction "1_1") (pintype "passive"))
      (node (ref "C338") (pin "2") (pinfunction "2_2") (pintype "passive"))
      (node (ref "D2") (pin "2E12") (pinfunction "PCIE1_SATA1_USB3_OTG1_AVDD1V8_2E12") (pintype "power_in"))
      (node (ref "D2") (pin "2F12") (pinfunction "PCIE0_SATA0_AVDD1V8_2F12") (pintype "power_in"))
      (node (ref "D2") (pin "2N10") (pinfunction "HDMI_TX_EDP_TX_AVDDIO1V8_2N10") (pintype "power_in"))
      (node (ref "D2") (pin "2N4") (pinfunction "USB3_OTG0_DP_TX_AVDD1V8_2N4") (pintype "power_in"))
      (node (ref "D2") (pin "2P10") (pinfunction "HDMI_TX_EDP_TX_AVDDCMN1V8_2P10") (pintype "power_in"))
      (node (ref "D2") (pin "2P4") (pinfunction "USB2_OTG_AVDD1V8_2P4") (pintype "power_in"))
      (node (ref "R167") (pin "1") (pinfunction "1_1") (pintype "passive"))
    )
    (net (code "187") (name "VCC_3V3_S0") (class "Default")
      (node (ref "C323") (pin "2") (pinfunction "2_2") (pintype "passive"))
      (node (ref "D2") (pin "2P7") (pinfunction "USB2_OTG_AVDD3V3_2P7") (pintype "power_in"))
    )
    (net (code "188") (name "VDDA_0V75_S0") (class "Default")
      (node (ref "C320") (pin "2") (pinfunction "2_2") (pintype "passive"))
      (node (ref "D2") (pin "2P5") (pinfunction "USB2_OTG_DVDD0V75_2P5") (pintype "power_in"))
    )
    (net (code "189") (name "VDDA_0V85_S0") (class "Default")
      (node (ref "C316") (pin "1") (pinfunction "1_1") (pintype "passive"))
      (node (ref "C324") (pin "2") (pinfunction "2_2") (pintype "passive"))
      (node (ref "C326") (pin "2") (pinfunction "2_2") (pintype "passive"))
      (node (ref "D2") (pin "2E11") (pinfunction "PCIE1_SATA1_USB3_OTG1_AVDD0V85_2E11") (pintype "power_in"))
      (node (ref "D2") (pin "2F11") (pinfunction "PCIE0_SATA0_AVDD0V85_2F11") (pintype "power_in"))
      (node (ref "D2") (pin "2M5") (pinfunction "USB3_OTG0_DP_TX_AVDD0V85_2M5") (pintype "power_in"))
      (node (ref "D2") (pin "2N5") (pinfunction "USB3_OTG0_DP_TX_DVDD0V85_2N5") (pintype "power_in"))
    )
    (net (code "190") (name "VDDA_HDMI_S0") (class "Default")
      (node (ref "C327") (pin "2") (pinfunction "2_2") (pintype "passive"))
      (node (ref "C328") (pin "1") (pinfunction "1_1") (pintype "passive"))
      (node (ref "D2") (pin "2N11") (pinfunction "HDMI_TX_EDP_TX_AVDDD0V75_2N11") (pintype "power_in"))
      (node (ref "D2") (pin "2P11") (pinfunction "HDMI_TX_EDP_TX_AVDDC0V75_2P11") (pintype "power_in"))
    )
    (net (code "191") (name "unconnected-(D2E-DP_TX_AUXN-Pad2T3)") (class "Default")
      (node (ref "D2") (pin "2T3") (pinfunction "DP_TX_AUXN_2T3") (pintype "output+no_connect"))
    )
    (net (code "192") (name "unconnected-(D2E-DP_TX_AUXP-Pad2T2)") (class "Default")
      (node (ref "D2") (pin "2T2") (pinfunction "DP_TX_AUXP_2T2") (pintype "output+no_connect"))
    )
    (net (code "193") (name "unconnected-(D2E-USB2_OTG1_ID-Pad2T9)") (class "Default")
      (node (ref "D2") (pin "2T9") (pinfunction "USB2_OTG1_ID_2T9") (pintype "passive+no_connect"))
    )
    (net (code "194") (name "unconnected-(D2E-USB2_OTG1_VBUSDET-Pad2T10)") (class "Default")
      (node (ref "D2") (pin "2T10") (pinfunction "USB2_OTG1_VBUSDET_2T10") (pintype "passive+no_connect"))
    )
    (net (code "195") (name "unconnected-(D2E-USB3_OTG0_SSRX2N-PadAL12)") (class "Default")
      (node (ref "D2") (pin "AL12") (pinfunction "USB3_OTG0_SSRX2N_AL12") (pintype "bidirectional+no_connect"))
    )
    (net (code "196") (name "unconnected-(D2E-USB3_OTG0_SSRX2P-PadAK12)") (class "Default")
      (node (ref "D2") (pin "AK12") (pinfunction "USB3_OTG0_SSRX2P_AK12") (pintype "bidirectional+no_connect"))
    )
    (net (code "197") (name "unconnected-(D2E-USB3_OTG0_SSTX2N-PadAK13)") (class "Default")
      (node (ref "D2") (pin "AK13") (pinfunction "USB3_OTG0_SSTX2N_AK13") (pintype "output+no_connect"))
    )
    (net (code "198") (name "unconnected-(D2E-USB3_OTG0_SSTX2P-PadAL13)") (class "Default")
      (node (ref "D2") (pin "AL13") (pinfunction "USB3_OTG0_SSTX2P_AL13") (pintype "output+no_connect"))
    )
    (net (code "199") (name "unconnected-(D21B-MSCLK-Pad6)") (class "Default")
      (node (ref "D21") (pin "6") (pinfunction "MSCLK_6") (pintype "power_in+no_connect"))
    )
    (net (code "200") (name "unconnected-(D21B-MSDA-Pad7)") (class "Default")
      (node (ref "D21") (pin "7") (pinfunction "MSDA_7") (pintype "power_in+no_connect"))
    )
    (net (code "201") (name "unconnected-(X16-+1.5V-Pad28)") (class "Default")
      (node (ref "X16") (pin "28") (pinfunction "+1.5V_28") (pintype "passive+no_connect"))
    )
    (net (code "202") (name "unconnected-(X16-+3.3Vaux-Pad24)") (class "Default")
      (node (ref "X16") (pin "24") (pinfunction "+3.3Vaux_24") (pintype "passive+no_connect"))
    )
    (net (code "203") (name "unconnected-(X16-+3.3Vaux-Pad39)") (class "Default")
      (node (ref "X16") (pin "39") (pinfunction "+3.3Vaux_39") (pintype "passive+no_connect"))
    )
    (net (code "204") (name "unconnected-(X16-+3.3Vaux-Pad41)") (class "Default")
      (node (ref "X16") (pin "41") (pinfunction "+3.3Vaux_41") (pintype "passive+no_connect"))
    )
    (net (code "205") (name "unconnected-(X16-+3.3Vaux-Pad52)") (class "Default")
      (node (ref "X16") (pin "52") (pinfunction "+3.3Vaux_52") (pintype "passive+no_connect"))
    )
    (net (code "206") (name "unconnected-(X16-3.3Vaux-Pad2)") (class "Default")
      (node (ref "X16") (pin "2") (pinfunction "3.3Vaux_2") (pintype "passive+no_connect"))
    )
    (net (code "207") (name "unconnected-(X16-CLKREQ#-Pad7)") (class "Default")
      (node (ref "X16") (pin "7") (pinfunction "CLKREQ#_7") (pintype "passive+no_connect"))
    )
    (net (code "208") (name "unconnected-(X16-GND-Pad4)") (class "Default")
      (node (ref "X16") (pin "4") (pinfunction "GND_4") (pintype "passive+no_connect"))
    )
    (net (code "209") (name "unconnected-(X16-GND-Pad9)") (class "Default")
      (node (ref "X16") (pin "9") (pinfunction "GND_9") (pintype "passive+no_connect"))
    )
    (net (code "210") (name "unconnected-(X16-GND-Pad15)") (class "Default")
      (node (ref "X16") (pin "15") (pinfunction "GND_15") (pintype "passive+no_connect"))
    )
    (net (code "211") (name "unconnected-(X16-GND-Pad18)") (class "Default")
      (node (ref "X16") (pin "18") (pinfunction "GND_18") (pintype "passive+no_connect"))
    )
    (net (code "212") (name "unconnected-(X16-GND-Pad21)") (class "Default")
      (node (ref "X16") (pin "21") (pinfunction "GND_21") (pintype "passive+no_connect"))
    )
    (net (code "213") (name "unconnected-(X16-LED_WLAN#-Pad44)") (class "Default")
      (node (ref "X16") (pin "44") (pinfunction "LED_WLAN#_44") (pintype "passive+no_connect"))
    )
    (net (code "214") (name "unconnected-(X16-LED_WPAN#-Pad46)") (class "Default")
      (node (ref "X16") (pin "46") (pinfunction "LED_WPAN#_46") (pintype "passive+no_connect"))
    )
    (net (code "215") (name "unconnected-(X16-LED_WWAN#-Pad42)") (class "Default")
      (node (ref "X16") (pin "42") (pinfunction "LED_WWAN#_42") (pintype "passive+no_connect"))
    )
    (net (code "216") (name "unconnected-(X16-Reserved-Pad17)") (class "Default")
      (node (ref "X16") (pin "17") (pinfunction "Reserved_17") (pintype "passive+no_connect"))
    )
    (net (code "217") (name "unconnected-(X16-Reserved-Pad19)") (class "Default")
      (node (ref "X16") (pin "19") (pinfunction "Reserved_19") (pintype "passive+no_connect"))
    )
    (net (code "218") (name "unconnected-(X16-Reserved-Pad45)") (class "Default")
      (node (ref "X16") (pin "45") (pinfunction "Reserved_45") (pintype "passive+no_connect"))
    )
    (net (code "219") (name "unconnected-(X16-Reserved-Pad47)") (class "Default")
      (node (ref "X16") (pin "47") (pinfunction "Reserved_47") (pintype "passive+no_connect"))
    )
    (net (code "220") (name "unconnected-(X16-Reserved-Pad49)") (class "Default")
      (node (ref "X16") (pin "49") (pinfunction "Reserved_49") (pintype "passive+no_connect"))
    )
    (net (code "221") (name "unconnected-(X16-Reserved-Pad51)") (class "Default")
      (node (ref "X16") (pin "51") (pinfunction "Reserved_51") (pintype "passive+no_connect"))
    )
    (net (code "222") (name "unconnected-(X16-USB_D+-Pad38)") (class "Default")
      (node (ref "X16") (pin "38") (pinfunction "USB_D+_38") (pintype "passive"))
    )
    (net (code "223") (name "unconnected-(X16-USB_D--Pad36)") (class "Default")
      (node (ref "X16") (pin "36") (pinfunction "USB_D-_36") (pintype "passive"))
    )
    (net (code "224") (name "unconnected-(X16-W_DISABLE#-Pad20)") (class "Default")
      (node (ref "X16") (pin "20") (pinfunction "W_DISABLE#_20") (pintype "passive+no_connect"))
    )
    (net (code "225") (name "unconnected-(X16-СОЕХ2-Pad5)") (class "Default")
      (node (ref "X16") (pin "5") (pinfunction "СОЕХ2_5") (pintype "passive+no_connect"))
    )
    (net (code "226") (name "unconnected-(X17-3.3Vaux-Pad2)") (class "Default")
      (node (ref "X17") (pin "2") (pinfunction "3.3Vaux_2") (pintype "passive+no_connect"))
    )
    (net (code "227") (name "unconnected-(X17-CLKREQ#-Pad7)") (class "Default")
      (node (ref "X17") (pin "7") (pinfunction "CLKREQ#_7") (pintype "passive+no_connect"))
    )
    (net (code "228") (name "unconnected-(X17-WAKE#-Pad1)") (class "Default")
      (node (ref "X17") (pin "1") (pinfunction "WAKE#_1") (pintype "passive+no_connect"))
    )
    (net (code "229") (name "unconnected-(X17-СОЕХ1-Pad3)") (class "Default")
      (node (ref "X17") (pin "3") (pinfunction "СОЕХ1_3") (pintype "passive+no_connect"))
    )
    (net (code "230") (name "unconnected-(X17-СОЕХ2-Pad5)") (class "Default")
      (node (ref "X17") (pin "5") (pinfunction "СОЕХ2_5") (pintype "passive+no_connect"))
    )
    (net (code "231") (name "unconnected-(X18-GND-PadA15)") (class "Default")
      (node (ref "X18") (pin "A15") (pinfunction "GND_A15") (pintype "passive+no_connect"))
    )
    (net (code "232") (name "unconnected-(X19-+3.3V-AUX-PadB10)") (class "Default")
      (node (ref "X19") (pin "B10") (pinfunction "+3.3V-AUX_B10") (pintype "passive+no_connect"))
    )
    (net (code "233") (name "unconnected-(X19-+3.3V-PadA9)") (class "Default")
      (node (ref "X19") (pin "A9") (pinfunction "+3.3V_A9") (pintype "passive+no_connect"))
    )
    (net (code "234") (name "unconnected-(X19-+3.3V-PadA10)") (class "Default")
      (node (ref "X19") (pin "A10") (pinfunction "+3.3V_A10") (pintype "passive+no_connect"))
    )
    (net (code "235") (name "unconnected-(X19-+3.3V-PadB8)") (class "Default")
      (node (ref "X19") (pin "B8") (pinfunction "+3.3V_B8") (pintype "passive+no_connect"))
    )
    (net (code "236") (name "unconnected-(X19-GND-PadA4)") (class "Default")
      (node (ref "X19") (pin "A4") (pinfunction "GND_A4") (pintype "passive+no_connect"))
    )
    (net (code "237") (name "unconnected-(X19-GND-PadA12)") (class "Default")
      (node (ref "X19") (pin "A12") (pinfunction "GND_A12") (pintype "passive+no_connect"))
    )
    (net (code "238") (name "unconnected-(X19-GND-PadA15)") (class "Default")
      (node (ref "X19") (pin "A15") (pinfunction "GND_A15") (pintype "passive+no_connect"))
    )
    (net (code "239") (name "unconnected-(X19-GND-PadB7)") (class "Default")
      (node (ref "X19") (pin "B7") (pinfunction "GND_B7") (pintype "passive+no_connect"))
    )
    (net (code "240") (name "unconnected-(X19-JTAG1-TRST#-PadB9)") (class "Default")
      (node (ref "X19") (pin "B9") (pinfunction "JTAG1-TRST#_B9") (pintype "passive+no_connect"))
    )
    (net (code "241") (name "unconnected-(X19-JTAG2-TCK-PadA5)") (class "Default")
      (node (ref "X19") (pin "A5") (pinfunction "JTAG2-TCK_A5") (pintype "passive+no_connect"))
    )
    (net (code "242") (name "unconnected-(X19-JTAG3-TDI-PadA6)") (class "Default")
      (node (ref "X19") (pin "A6") (pinfunction "JTAG3-TDI_A6") (pintype "passive+no_connect"))
    )
    (net (code "243") (name "unconnected-(X19-JTAG4-TDO-PadA7)") (class "Default")
      (node (ref "X19") (pin "A7") (pinfunction "JTAG4-TDO_A7") (pintype "passive+no_connect"))
    )
    (net (code "244") (name "unconnected-(X19-JTAG5-TMS-PadA8)") (class "Default")
      (node (ref "X19") (pin "A8") (pinfunction "JTAG5-TMS_A8") (pintype "passive+no_connect"))
    )
    (net (code "245") (name "unconnected-(X19-PRSNT1#-PadA1)") (class "Default")
      (node (ref "X19") (pin "A1") (pinfunction "PRSNT1#_A1") (pintype "passive+no_connect"))
    )
  )
)
